# PKG900000001464.net
KiCad netlist of a schematic drawn in EAGLE
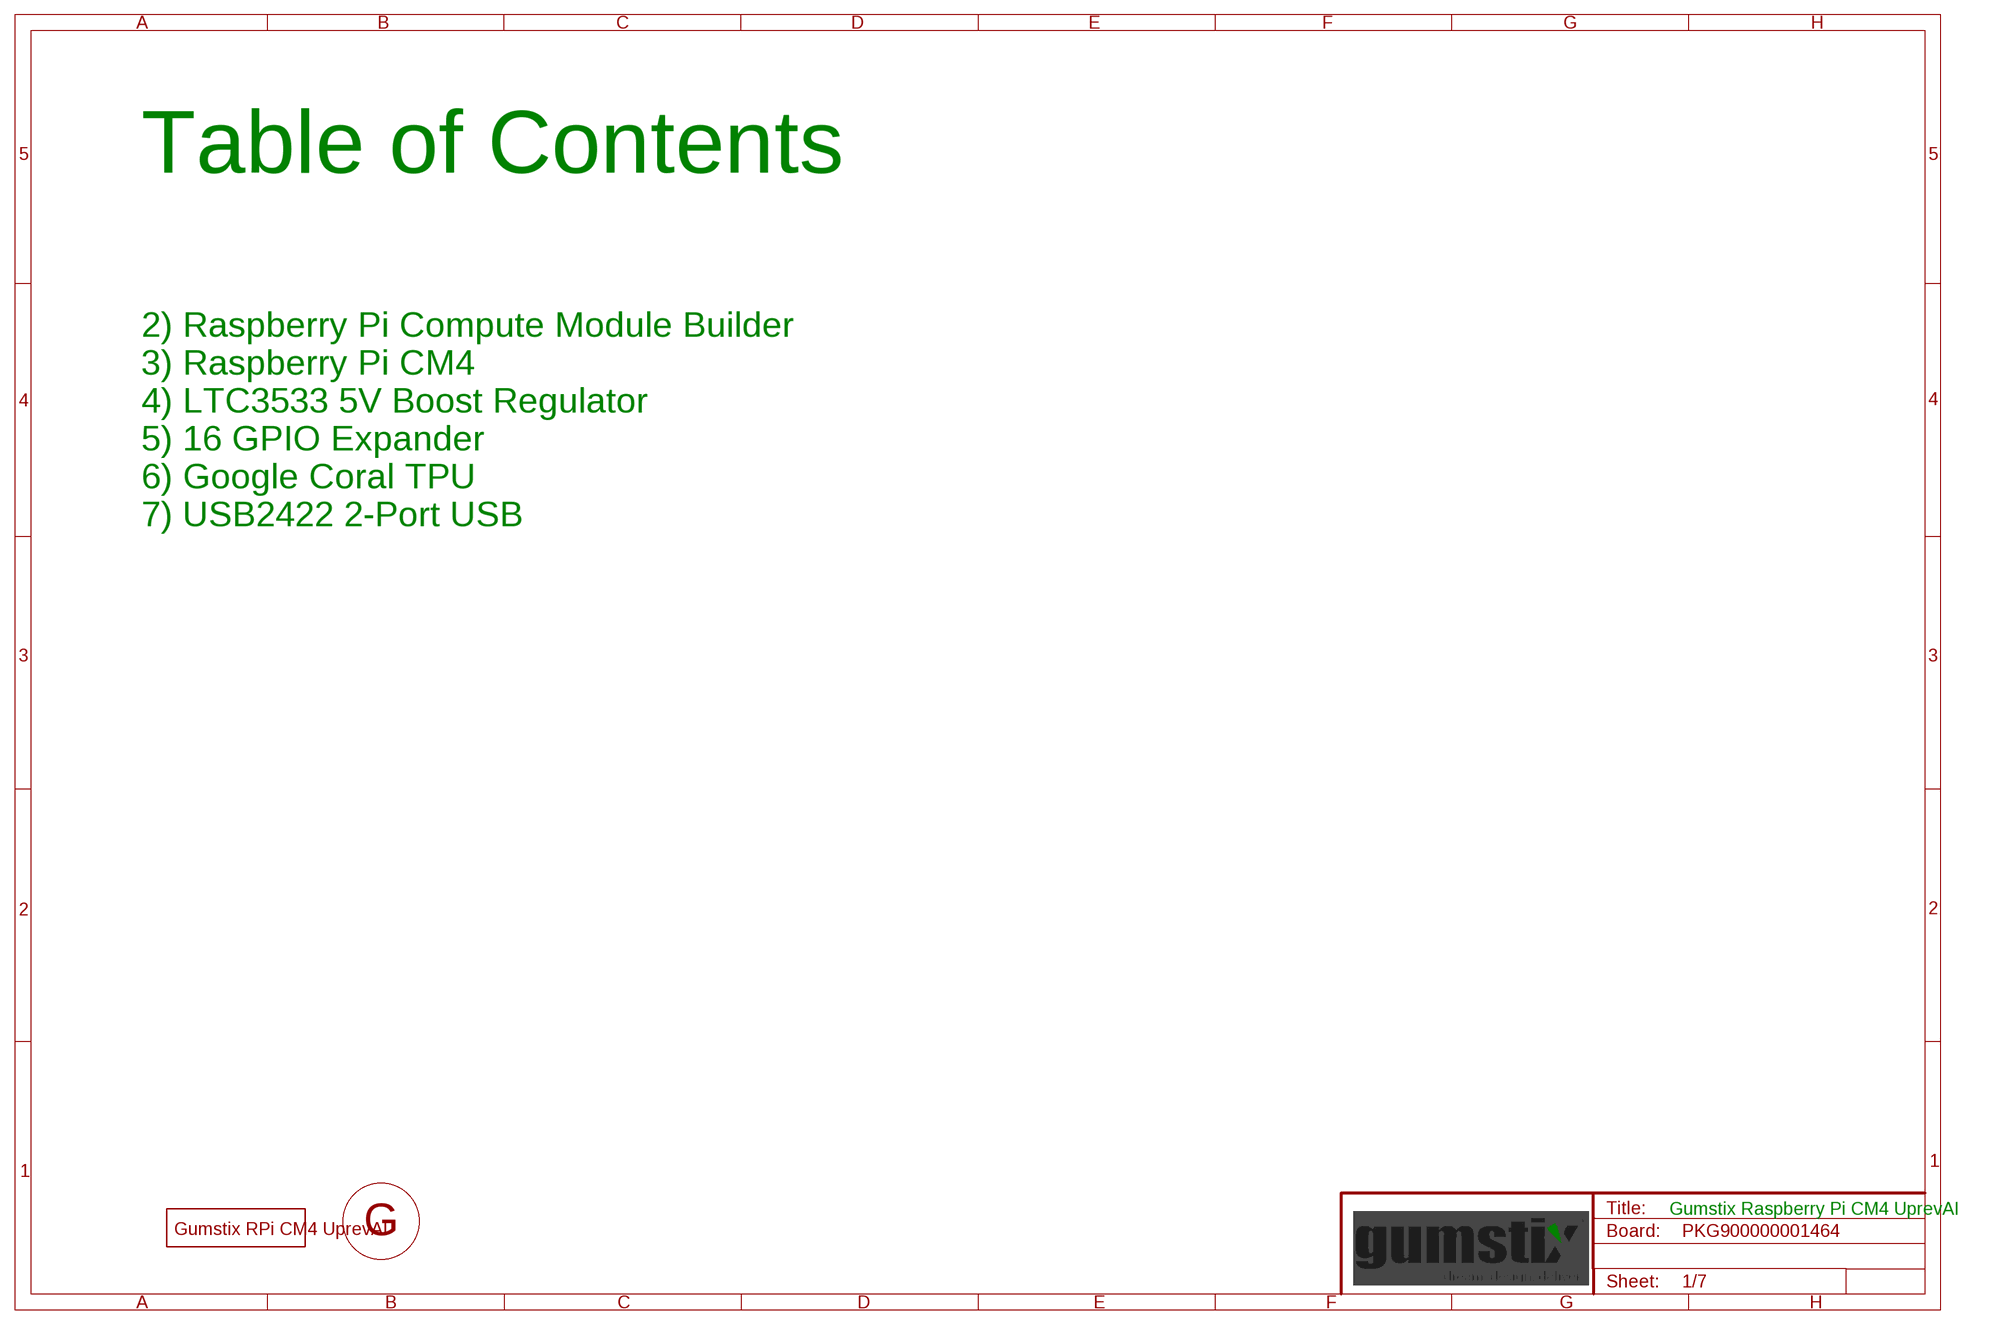
[diagram p0: schematic, sheet 1]
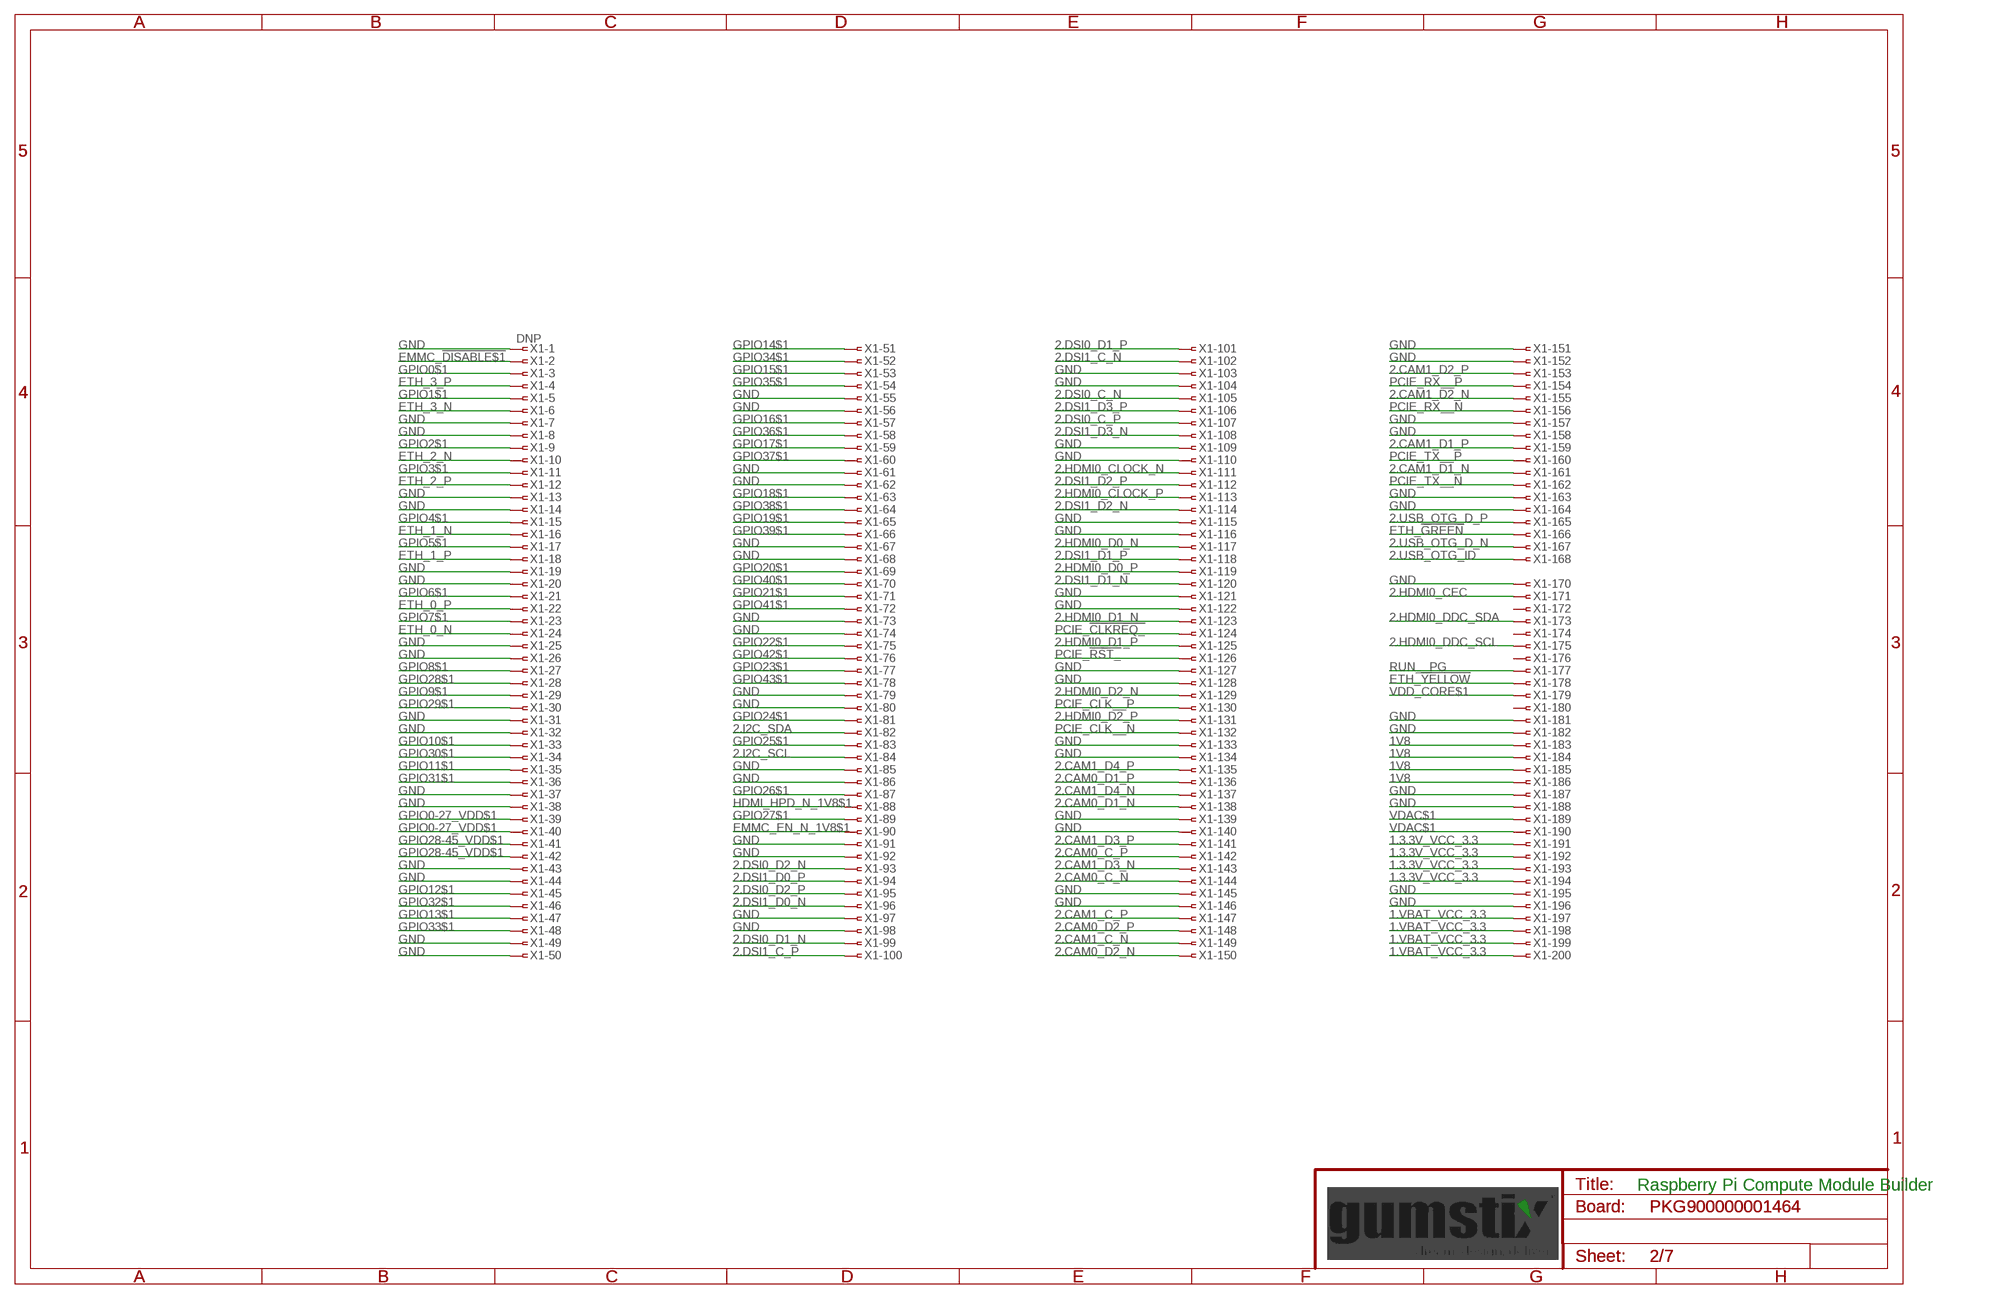
[diagram p1: schematic, sheet 2]
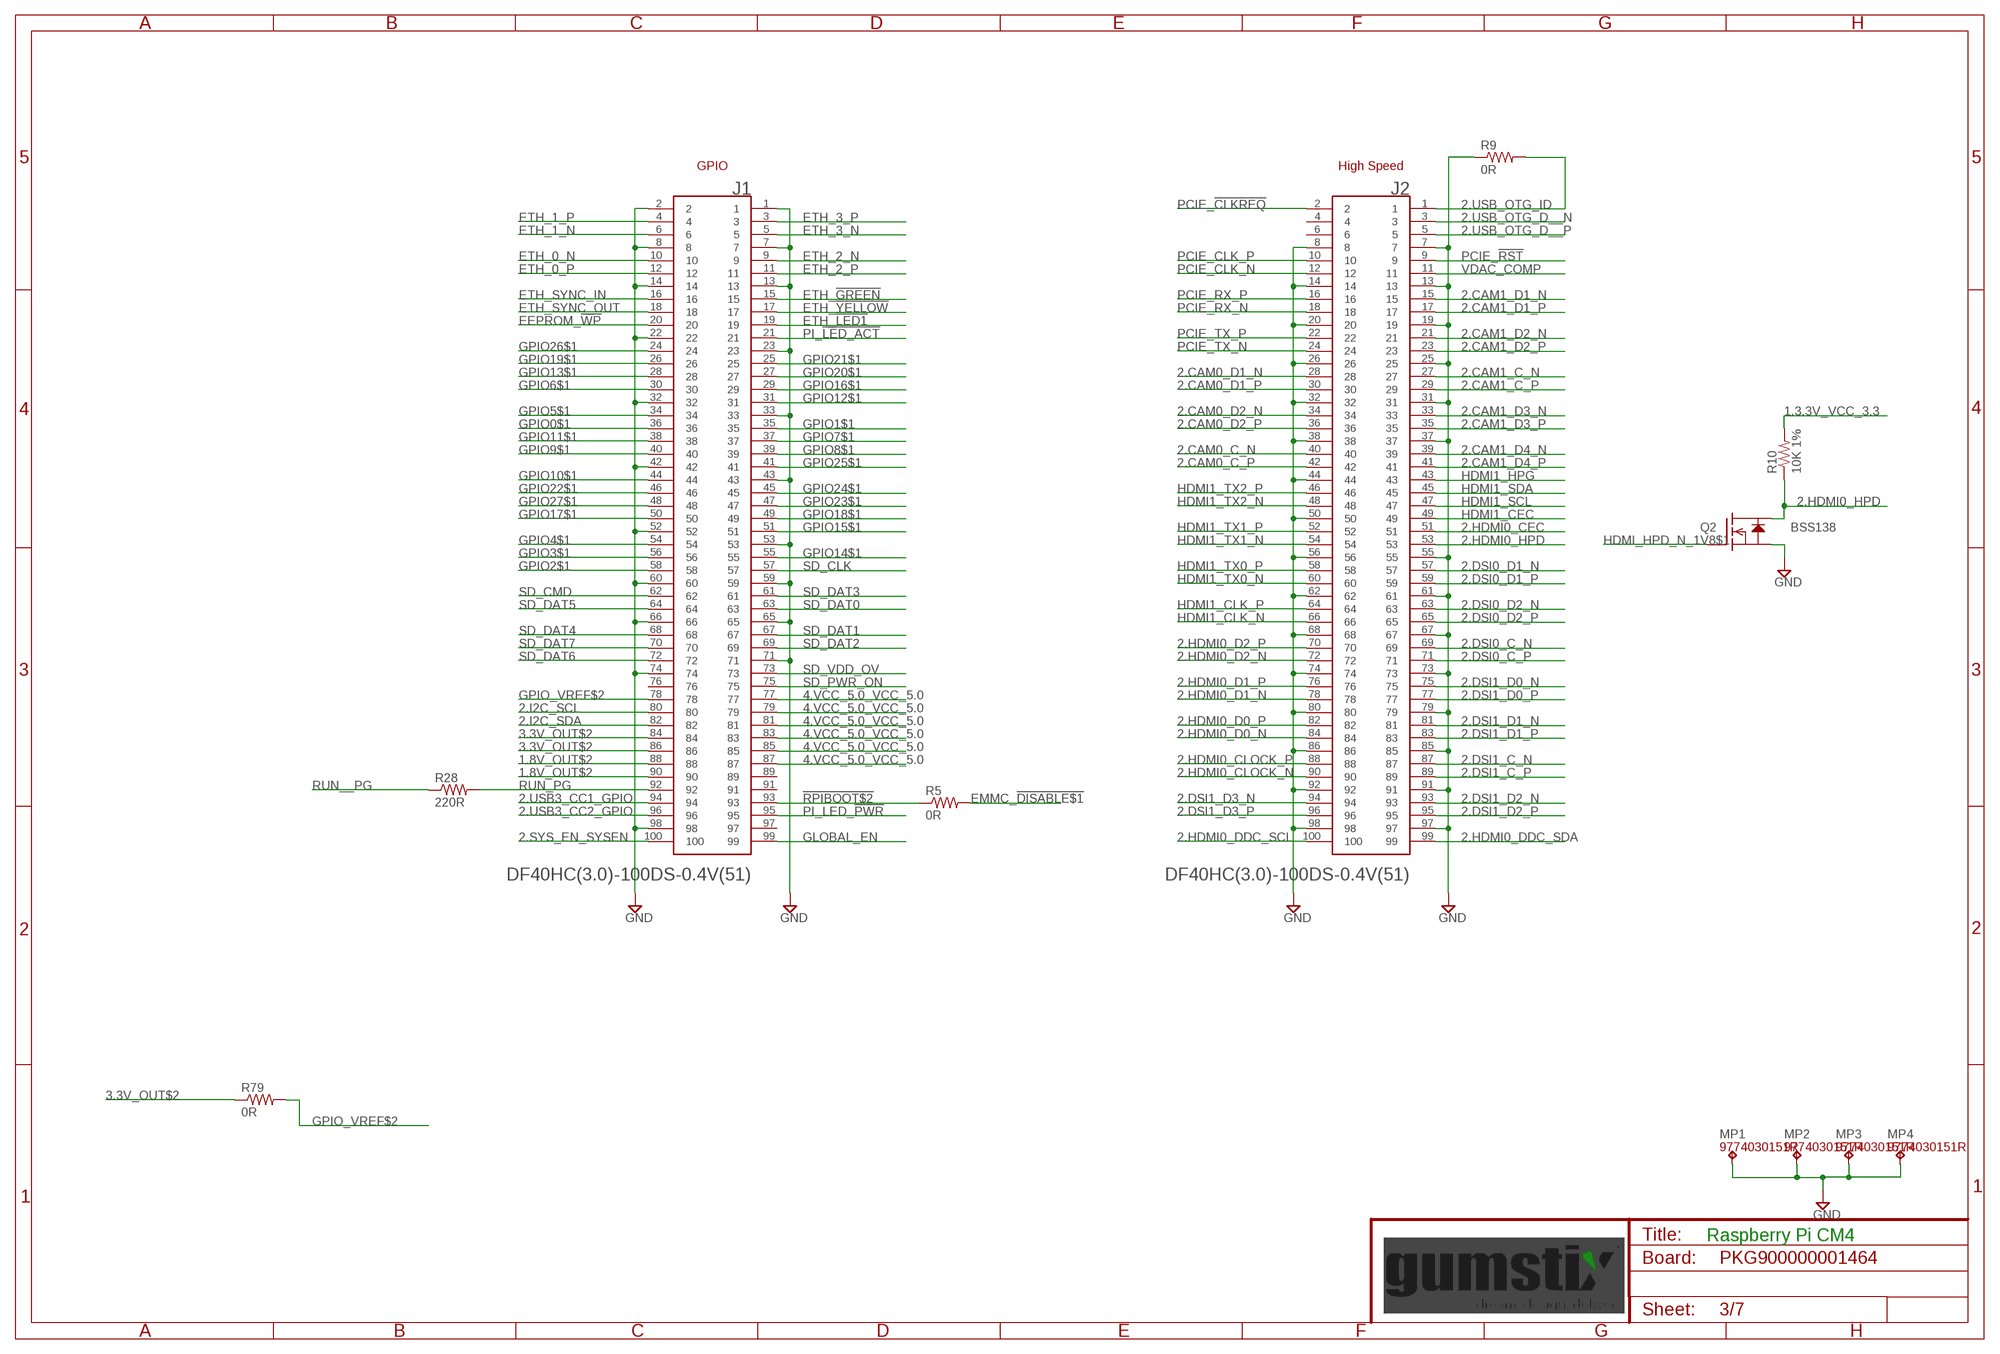
[diagram p2: schematic, sheet 3]
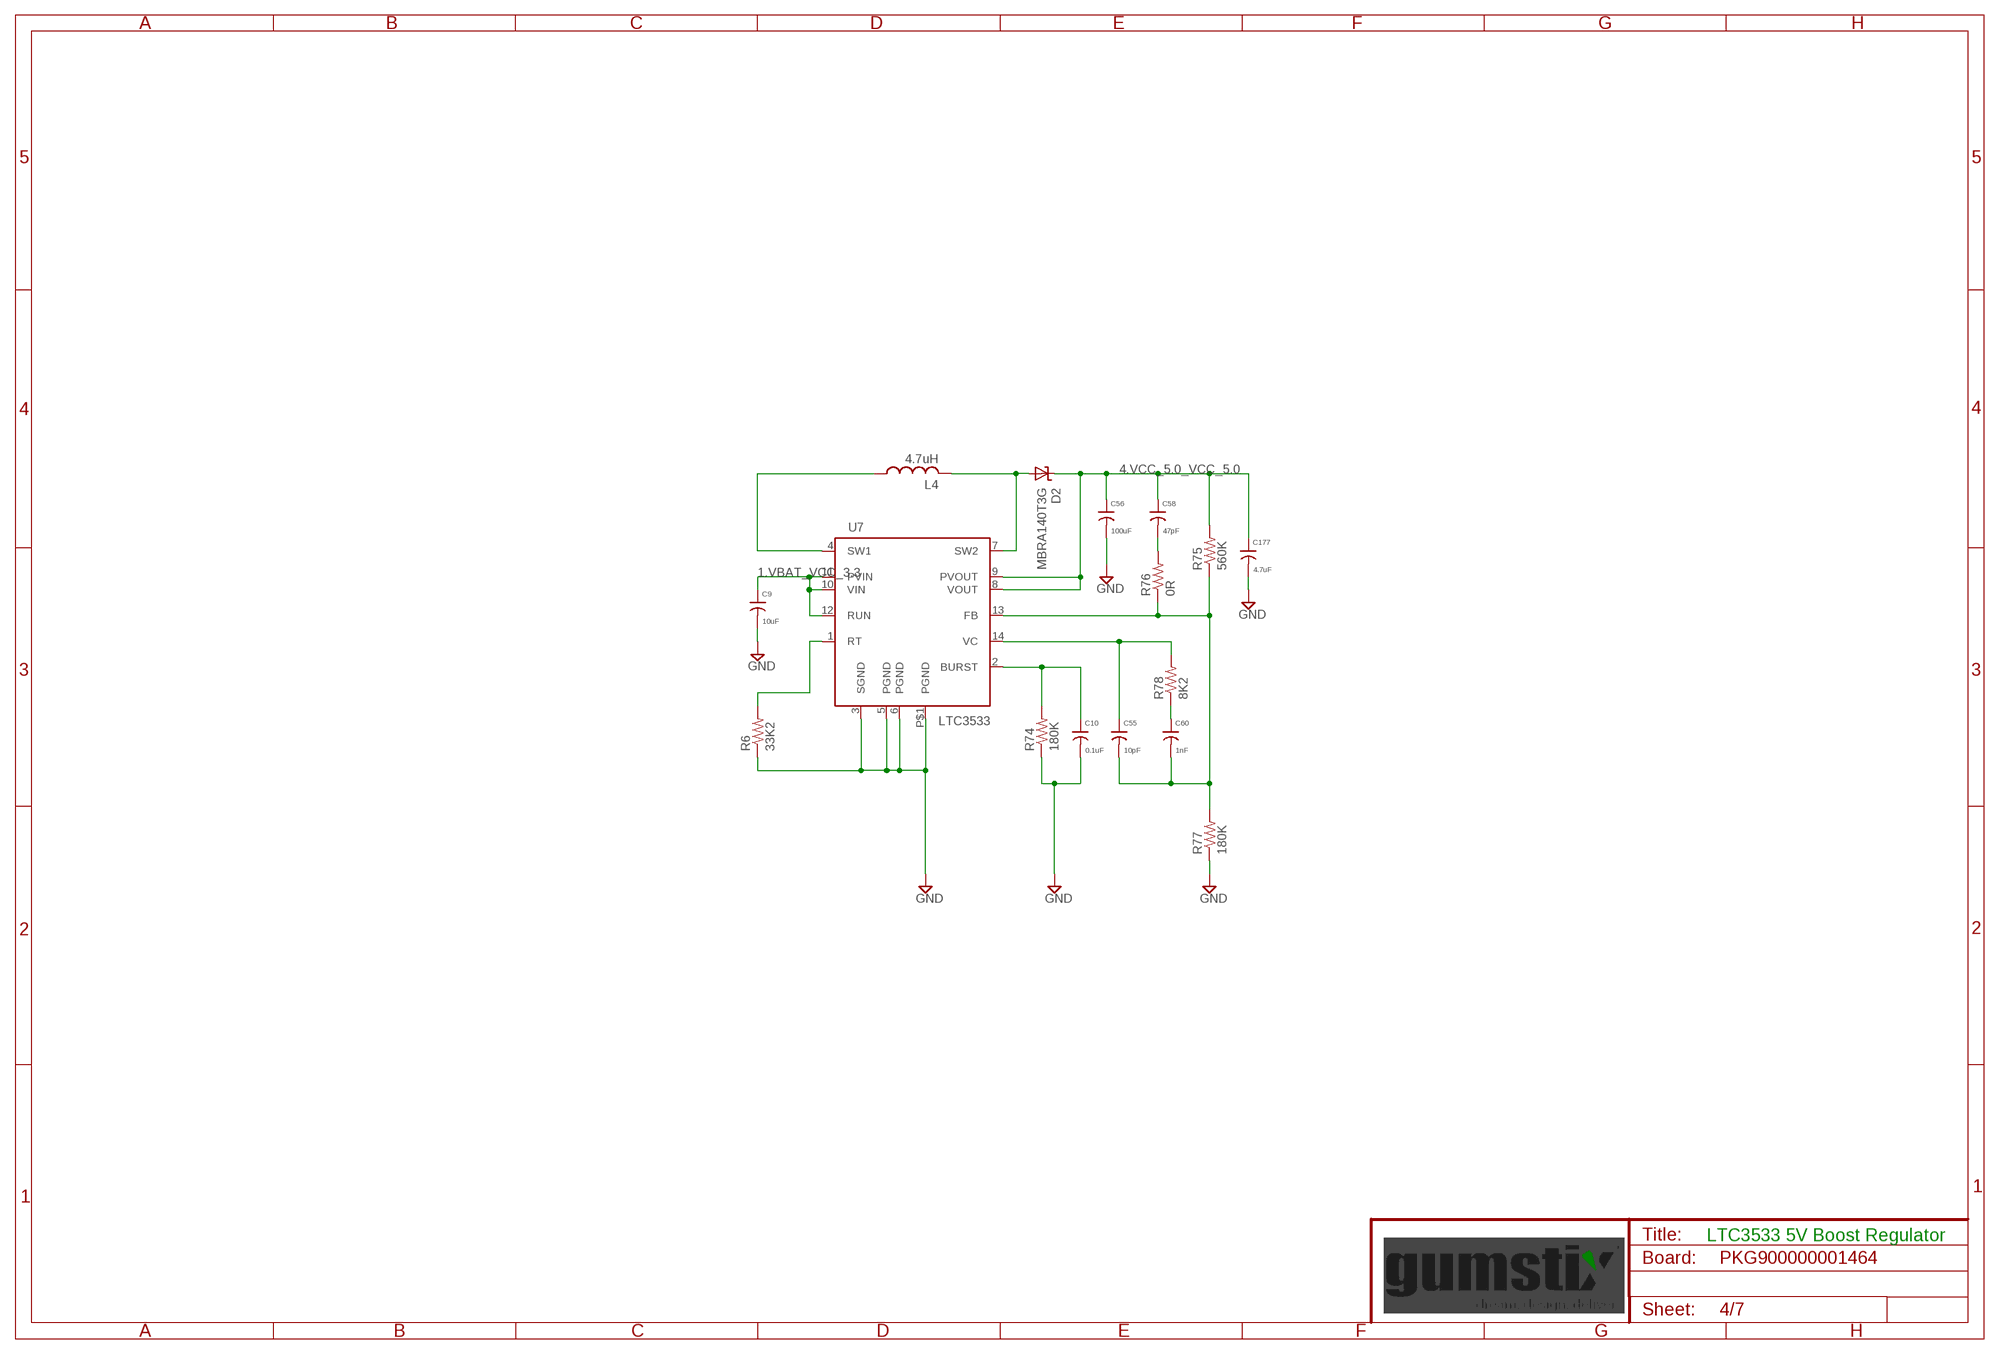
[diagram p3: schematic, sheet 4]
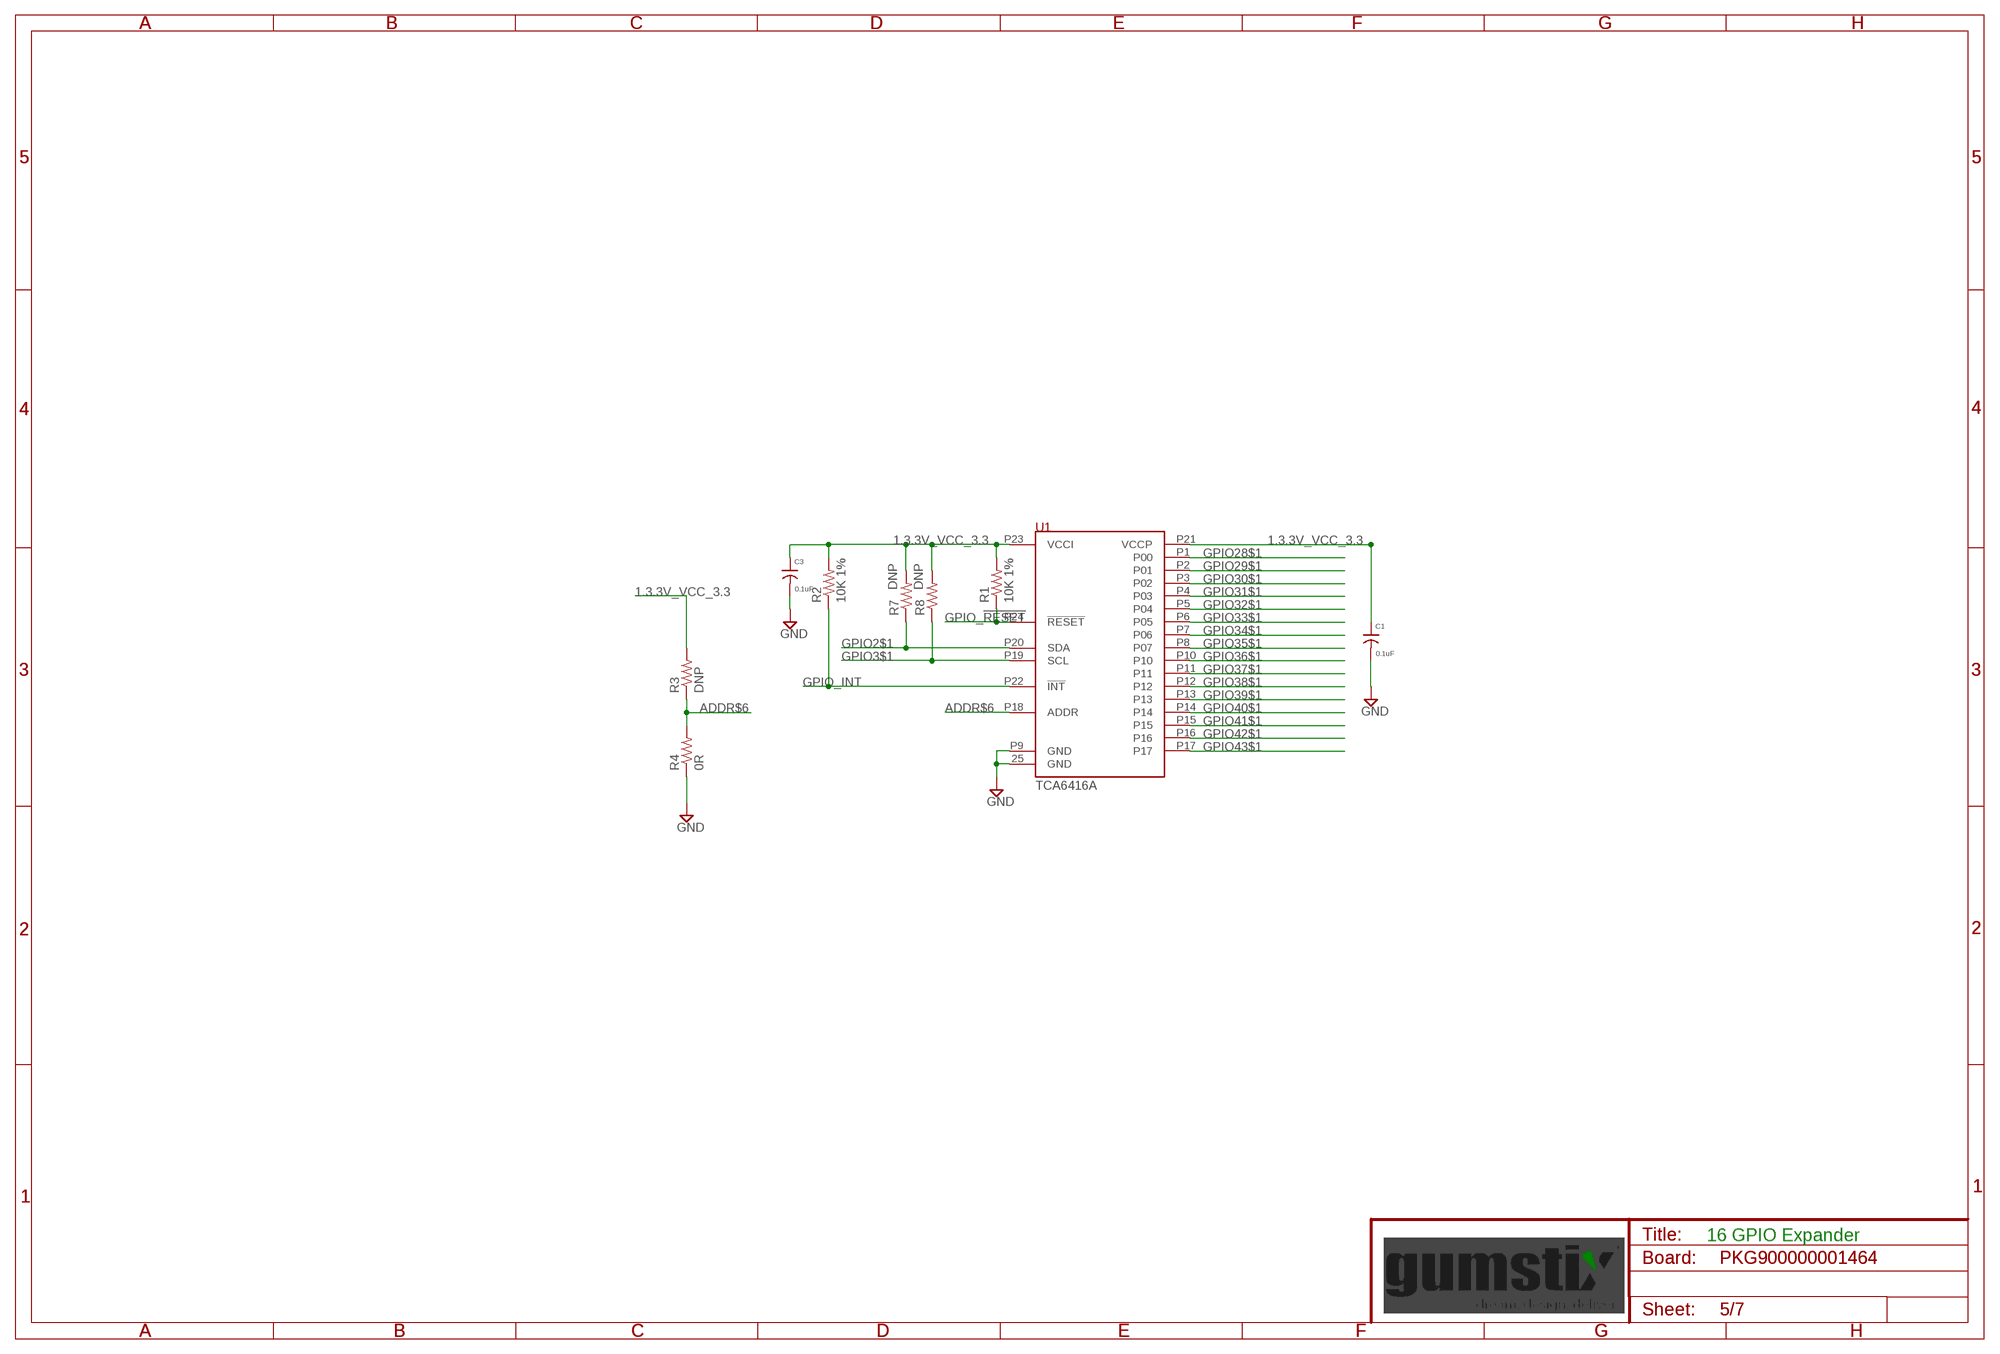
[diagram p4: schematic, sheet 5]
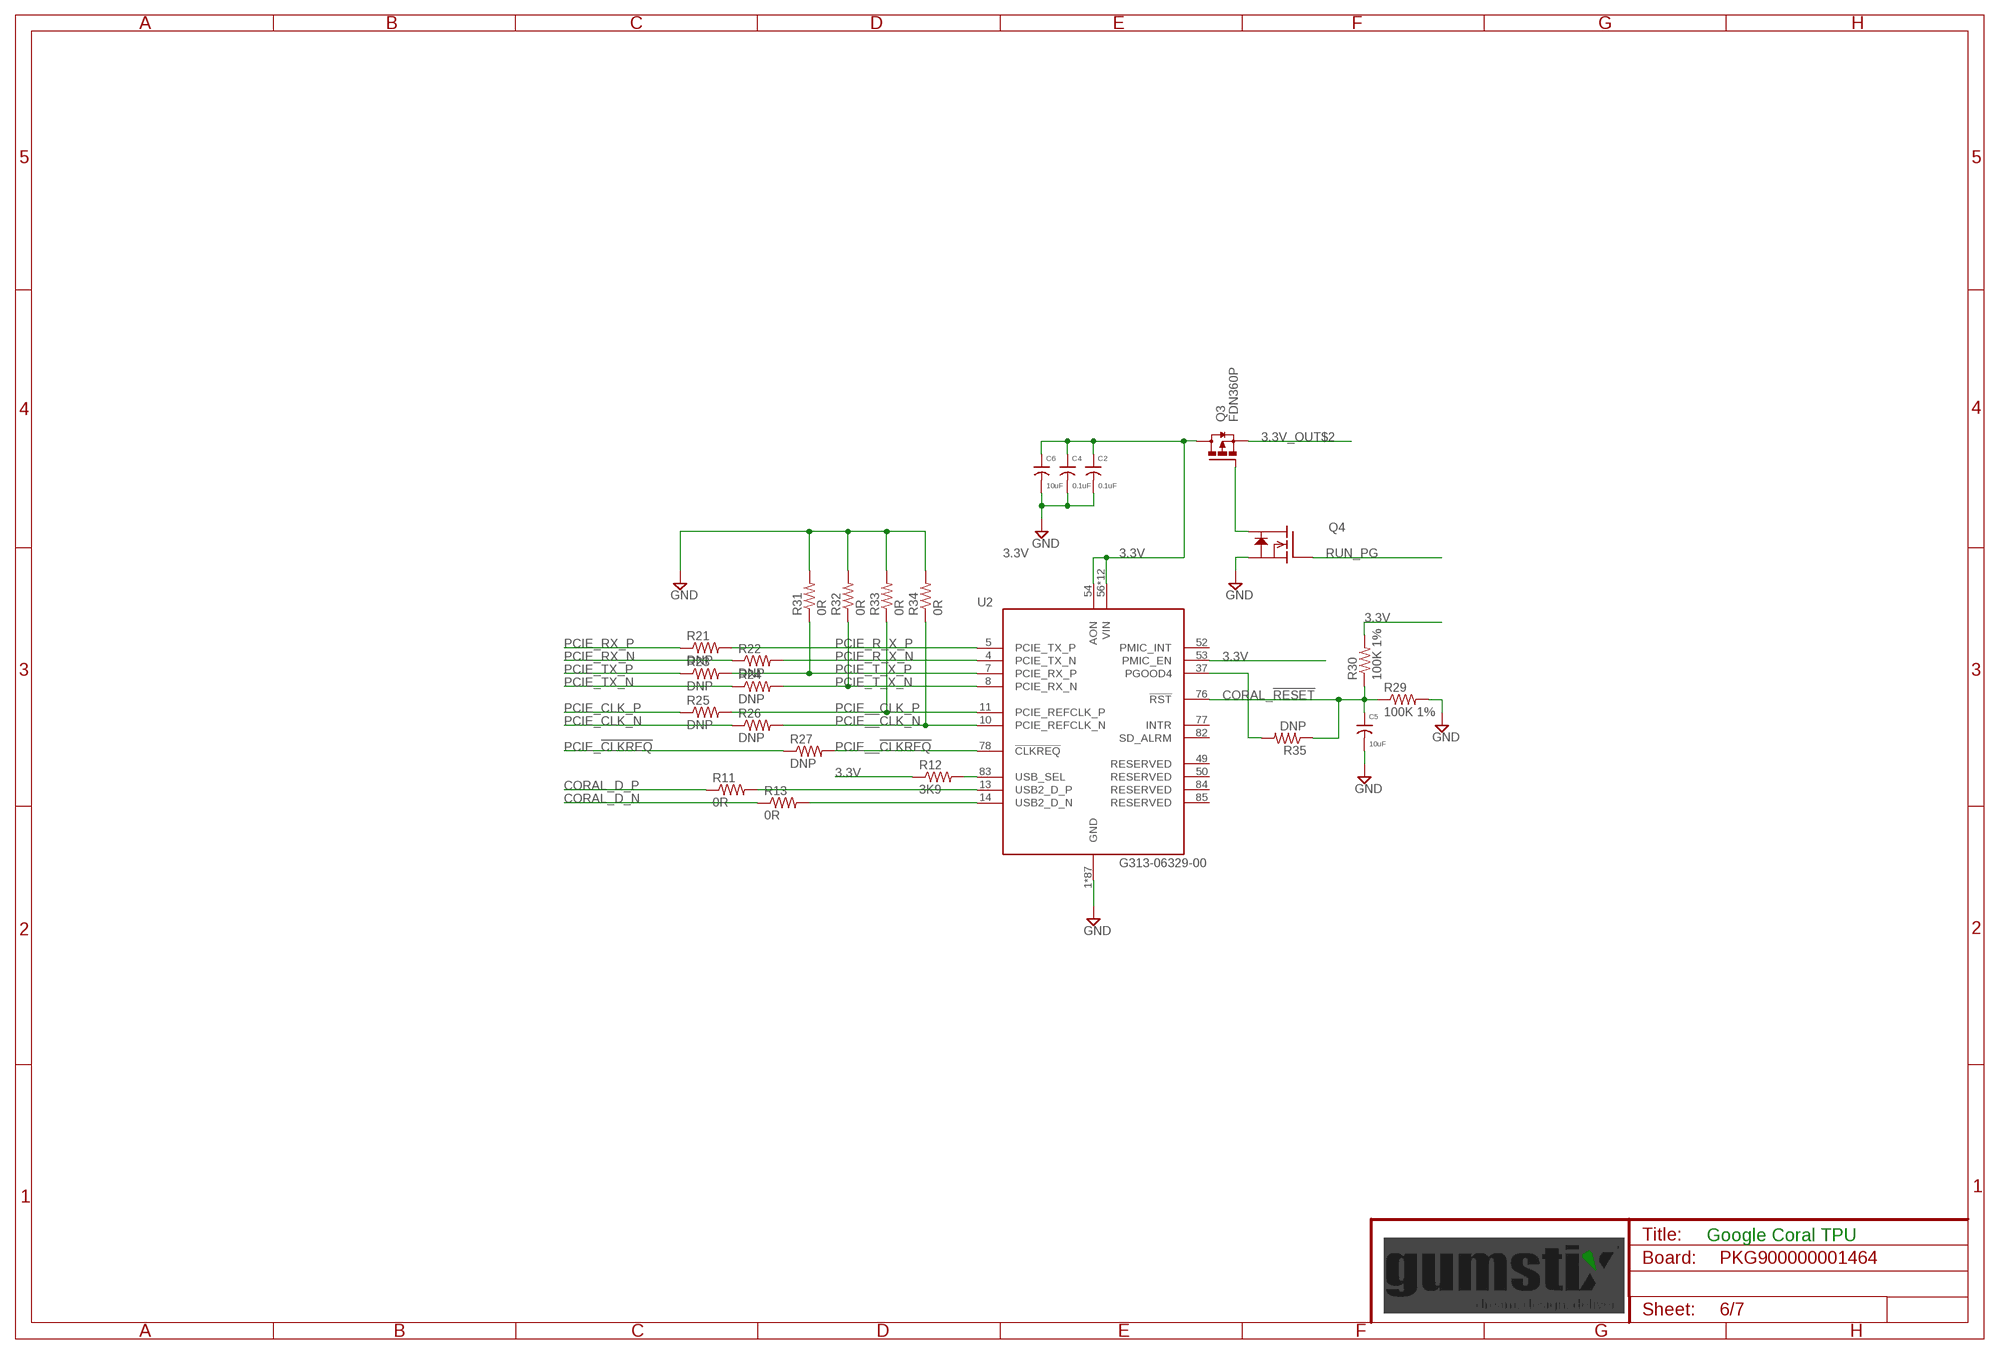
[diagram p5: schematic, sheet 6]
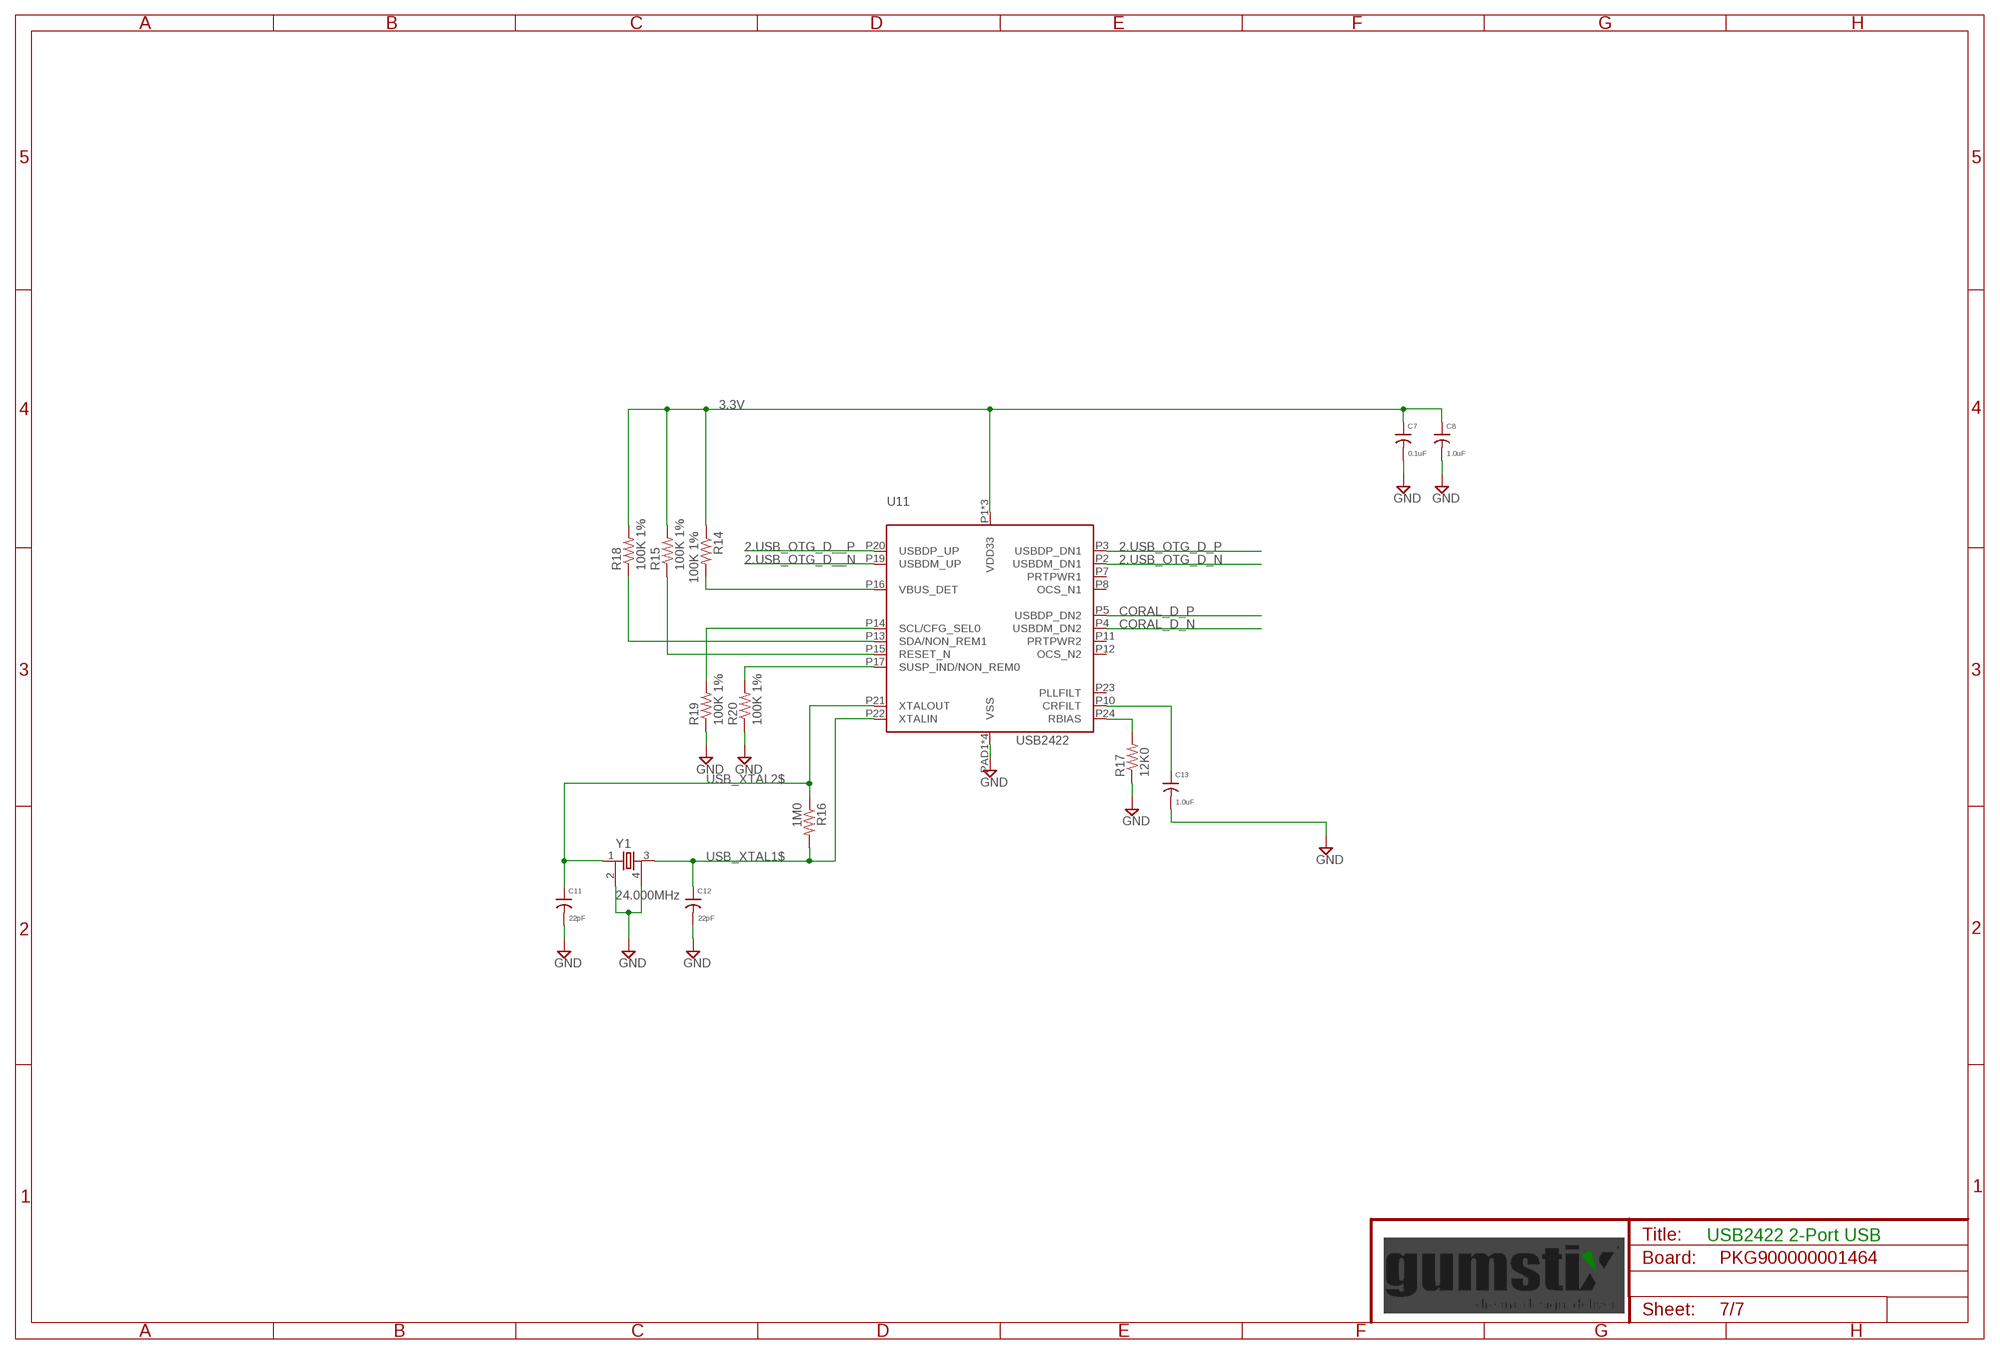
[diagram p6: schematic, sheet 7]

(export (version "E")
  (design (tool "Eeschema 10.0.6"))
  (components
    (comp (ref "C9")
      (value "10uF")
      (footprint "eagle-import:0603")
      (libsource (lib "eagle-import") (part "C0603"))
    )
    (comp (ref "C10")
      (value "0.1uF")
      (footprint "eagle-import:0201")
      (libsource (lib "eagle-import") (part "C0201"))
    )
    (comp (ref "C55")
      (value "10pF")
      (footprint "eagle-import:0201")
      (libsource (lib "eagle-import") (part "C0201"))
    )
    (comp (ref "C56")
      (value "100uF")
      (footprint "eagle-import:1206")
      (libsource (lib "eagle-import") (part "C1206"))
    )
    (comp (ref "C58")
      (value "47pF")
      (footprint "eagle-import:0201")
      (libsource (lib "eagle-import") (part "C0201"))
    )
    (comp (ref "C60")
      (value "1nF")
      (footprint "eagle-import:0402")
      (libsource (lib "eagle-import") (part "C0402"))
    )
    (comp (ref "C177")
      (value "4.7uF")
      (footprint "eagle-import:0603")
      (libsource (lib "eagle-import") (part "C0603"))
    )
    (comp (ref "D2")
      (value "MBRA140T3G")
      (footprint "eagle-import:SMAJ")
      (libsource (lib "eagle-import") (part "DSMA"))
    )
    (comp (ref "L4")
      (value "4.7uH")
      (footprint "eagle-import:B82462")
      (libsource (lib "eagle-import") (part "L82462"))
    )
    (comp (ref "R6")
      (value "33K2")
      (footprint "eagle-import:0402")
      (libsource (lib "eagle-import") (part "R0402"))
    )
    (comp (ref "R74")
      (value "180K")
      (footprint "eagle-import:0201")
      (libsource (lib "eagle-import") (part "R0201"))
    )
    (comp (ref "R75")
      (value "560K")
      (footprint "eagle-import:0402")
      (libsource (lib "eagle-import") (part "R0402"))
    )
    (comp (ref "R76")
      (value "0R")
      (footprint "eagle-import:0201")
      (libsource (lib "eagle-import") (part "R0201"))
    )
    (comp (ref "R77")
      (value "180K")
      (footprint "eagle-import:0201")
      (libsource (lib "eagle-import") (part "R0201"))
    )
    (comp (ref "R78")
      (value "8K2")
      (footprint "eagle-import:0402")
      (libsource (lib "eagle-import") (part "R0402"))
    )
    (comp (ref "U7")
      (value "LTC3533")
      (footprint "eagle-import:DFN-14")
      (libsource (lib "eagle-import") (part "LTC3533"))
    )
    (comp (ref "C1")
      (value "0.1uF")
      (footprint "eagle-import:0201")
      (libsource (lib "eagle-import") (part "C0201"))
    )
    (comp (ref "C3")
      (value "0.1uF")
      (footprint "eagle-import:0201")
      (libsource (lib "eagle-import") (part "C0201"))
    )
    (comp (ref "R1")
      (value "10K 1%")
      (footprint "eagle-import:0201")
      (libsource (lib "eagle-import") (part "R0201"))
    )
    (comp (ref "R2")
      (value "10K 1%")
      (footprint "eagle-import:0201")
      (libsource (lib "eagle-import") (part "R0201"))
    )
    (comp (ref "R3")
      (value "DNP")
      (footprint "eagle-import:0201")
      (libsource (lib "eagle-import") (part "R0201"))
    )
    (comp (ref "R4")
      (value "0R")
      (footprint "eagle-import:0201")
      (libsource (lib "eagle-import") (part "R0201"))
    )
    (comp (ref "R7")
      (value "DNP")
      (footprint "eagle-import:0201")
      (libsource (lib "eagle-import") (part "R0201"))
    )
    (comp (ref "R8")
      (value "DNP")
      (footprint "eagle-import:0201")
      (libsource (lib "eagle-import") (part "R0201"))
    )
    (comp (ref "U1")
      (value "TCA6416A")
      (footprint "eagle-import:WQFN24")
      (libsource (lib "eagle-import") (part "TCA6416A"))
    )
    (comp (ref "C7")
      (value "0.1uF")
      (footprint "eagle-import:0201")
      (libsource (lib "eagle-import") (part "C0201"))
    )
    (comp (ref "C8")
      (value "1.0uF")
      (footprint "eagle-import:0402")
      (libsource (lib "eagle-import") (part "C0402"))
    )
    (comp (ref "C11")
      (value "22pF")
      (footprint "eagle-import:0201")
      (libsource (lib "eagle-import") (part "C0201"))
    )
    (comp (ref "C12")
      (value "22pF")
      (footprint "eagle-import:0201")
      (libsource (lib "eagle-import") (part "C0201"))
    )
    (comp (ref "C13")
      (value "1.0uF")
      (footprint "eagle-import:0402")
      (libsource (lib "eagle-import") (part "C0402"))
    )
    (comp (ref "R14")
      (value "100K 1%")
      (footprint "eagle-import:0201")
      (libsource (lib "eagle-import") (part "R0201"))
    )
    (comp (ref "R15")
      (value "100K 1%")
      (footprint "eagle-import:0201")
      (libsource (lib "eagle-import") (part "R0201"))
    )
    (comp (ref "R16")
      (value "1M0")
      (footprint "eagle-import:0201")
      (libsource (lib "eagle-import") (part "R0201"))
    )
    (comp (ref "R17")
      (value "12K0")
      (footprint "eagle-import:0201")
      (libsource (lib "eagle-import") (part "R0201"))
    )
    (comp (ref "R18")
      (value "100K 1%")
      (footprint "eagle-import:0201")
      (libsource (lib "eagle-import") (part "R0201"))
    )
    (comp (ref "R19")
      (value "100K 1%")
      (footprint "eagle-import:0201")
      (libsource (lib "eagle-import") (part "R0201"))
    )
    (comp (ref "R20")
      (value "100K 1%")
      (footprint "eagle-import:0201")
      (libsource (lib "eagle-import") (part "R0201"))
    )
    (comp (ref "U11")
      (value "USB2422")
      (footprint "eagle-import:VQFN24")
      (libsource (lib "eagle-import") (part "USB2422"))
    )
    (comp (ref "Y1")
      (value "24.000MHz")
      (footprint "eagle-import:CRYSTAL-3225")
      (libsource (lib "eagle-import") (part "Y4CRYSTAL-3225"))
    )
    (comp (ref "J1")
      (value "DF40HC(3.0)-100DS-0.4V(51)")
      (footprint "eagle-import:HRS_DF40C-100DS-0.4V(51)")
      (fields
        (field (name "DIGI-KEY_PART_NUMBER") "H11615CT-ND")
        (field (name "MF") "Hirose")
        (field (name "MP") "DF40C-100DS-0.4V_51_")
      )
      (libsource (lib "eagle-import") (part "DF40C-100DS-0.4V(51)"))
    )
    (comp (ref "J2")
      (value "DF40HC(3.0)-100DS-0.4V(51)")
      (footprint "eagle-import:HRS_DF40C-100DS-0.4V(51)")
      (fields
        (field (name "DIGI-KEY_PART_NUMBER") "H11615CT-ND")
        (field (name "MF") "Hirose")
        (field (name "MP") "DF40C-100DS-0.4V_51_")
      )
      (libsource (lib "eagle-import") (part "DF40C-100DS-0.4V(51)"))
    )
    (comp (ref "MP1")
      (value "9774030151R")
      (footprint "eagle-import:WA-SMSI_9774___151")
      (libsource (lib "eagle-import") (part "BULLET_CONN2.5MM"))
    )
    (comp (ref "MP2")
      (value "9774030151R")
      (footprint "eagle-import:WA-SMSI_9774___151")
      (libsource (lib "eagle-import") (part "BULLET_CONN2.5MM"))
    )
    (comp (ref "MP3")
      (value "9774030151R")
      (footprint "eagle-import:WA-SMSI_9774___151")
      (libsource (lib "eagle-import") (part "BULLET_CONN2.5MM"))
    )
    (comp (ref "MP4")
      (value "9774030151R")
      (footprint "eagle-import:WA-SMSI_9774___151")
      (libsource (lib "eagle-import") (part "BULLET_CONN2.5MM"))
    )
    (comp (ref "Q2")
      (value "BSS138")
      (footprint "eagle-import:SOT23")
      (libsource (lib "eagle-import") (part "BSS138"))
    )
    (comp (ref "R5")
      (value "0R")
      (footprint "eagle-import:0201")
      (libsource (lib "eagle-import") (part "R0201"))
    )
    (comp (ref "R9")
      (value "0R")
      (footprint "eagle-import:0201")
      (libsource (lib "eagle-import") (part "R0201"))
    )
    (comp (ref "R10")
      (value "10K 1%")
      (footprint "eagle-import:0201")
      (libsource (lib "eagle-import") (part "R0201"))
    )
    (comp (ref "R28")
      (value "220R")
      (footprint "eagle-import:0402")
      (libsource (lib "eagle-import") (part "R0402"))
    )
    (comp (ref "R79")
      (value "0R")
      (footprint "eagle-import:0201")
      (libsource (lib "eagle-import") (part "R0201"))
    )
    (comp (ref "C2")
      (value "0.1uF")
      (footprint "eagle-import:0201")
      (libsource (lib "eagle-import") (part "C0201"))
    )
    (comp (ref "C4")
      (value "0.1uF")
      (footprint "eagle-import:0201")
      (libsource (lib "eagle-import") (part "C0201"))
    )
    (comp (ref "C5")
      (value "10uF")
      (footprint "eagle-import:0603")
      (libsource (lib "eagle-import") (part "C0603"))
    )
    (comp (ref "C6")
      (value "10uF")
      (footprint "eagle-import:0603")
      (libsource (lib "eagle-import") (part "C0603"))
    )
    (comp (ref "Q3")
      (value "FDN360P")
      (footprint "eagle-import:SOT23")
      (libsource (lib "eagle-import") (part "MOSFET_P_ENH"))
    )
    (comp (ref "Q4")
      (value "BSS138")
      (footprint "eagle-import:SOT23")
      (libsource (lib "eagle-import") (part "BSS138"))
    )
    (comp (ref "R11")
      (value "0R")
      (footprint "eagle-import:0201")
      (libsource (lib "eagle-import") (part "R0201"))
    )
    (comp (ref "R12")
      (value "3K9")
      (footprint "eagle-import:0201")
      (libsource (lib "eagle-import") (part "R0201"))
    )
    (comp (ref "R13")
      (value "0R")
      (footprint "eagle-import:0201")
      (libsource (lib "eagle-import") (part "R0201"))
    )
    (comp (ref "R21")
      (value "DNP")
      (footprint "eagle-import:0201")
      (libsource (lib "eagle-import") (part "R0201"))
    )
    (comp (ref "R22")
      (value "DNP")
      (footprint "eagle-import:0201")
      (libsource (lib "eagle-import") (part "R0201"))
    )
    (comp (ref "R23")
      (value "DNP")
      (footprint "eagle-import:0201")
      (libsource (lib "eagle-import") (part "R0201"))
    )
    (comp (ref "R24")
      (value "DNP")
      (footprint "eagle-import:0201")
      (libsource (lib "eagle-import") (part "R0201"))
    )
    (comp (ref "R25")
      (value "DNP")
      (footprint "eagle-import:0201")
      (libsource (lib "eagle-import") (part "R0201"))
    )
    (comp (ref "R26")
      (value "DNP")
      (footprint "eagle-import:0201")
      (libsource (lib "eagle-import") (part "R0201"))
    )
    (comp (ref "R27")
      (value "DNP")
      (footprint "eagle-import:0201")
      (libsource (lib "eagle-import") (part "R0201"))
    )
    (comp (ref "R29")
      (value "100K 1%")
      (footprint "eagle-import:0201")
      (libsource (lib "eagle-import") (part "R0201"))
    )
    (comp (ref "R30")
      (value "100K 1%")
      (footprint "eagle-import:0201")
      (libsource (lib "eagle-import") (part "R0201"))
    )
    (comp (ref "R31")
      (value "0R")
      (footprint "eagle-import:0201")
      (libsource (lib "eagle-import") (part "R0201"))
    )
    (comp (ref "R32")
      (value "0R")
      (footprint "eagle-import:0201")
      (libsource (lib "eagle-import") (part "R0201"))
    )
    (comp (ref "R33")
      (value "0R")
      (footprint "eagle-import:0201")
      (libsource (lib "eagle-import") (part "R0201"))
    )
    (comp (ref "R34")
      (value "0R")
      (footprint "eagle-import:0201")
      (libsource (lib "eagle-import") (part "R0201"))
    )
    (comp (ref "R35")
      (value "DNP")
      (footprint "eagle-import:0201")
      (libsource (lib "eagle-import") (part "R0201"))
    )
    (comp (ref "U2")
      (value "G313-06329-00")
      (footprint "eagle-import:G313-06329-00")
      (libsource (lib "eagle-import") (part "G313-06329-00"))
    )
    (comp (ref "X1")
      (value "DNP")
      (footprint "eagle-import:SLOT-1376408-1_1.8V_MOD")
      (libsource (lib "eagle-import") (part "1376408SLOT_1.8V_MOD"))
    )
    (comp (ref "FD1")
      (value "DNP")
      (footprint "eagle-import:FIDUCIAL")
      (libsource (lib "eagle-import") (part "FIDUCIAL"))
    )
    (comp (ref "FD2")
      (value "DNP")
      (footprint "eagle-import:FIDUCIAL")
      (libsource (lib "eagle-import") (part "FIDUCIAL"))
    )
    (comp (ref "FD3")
      (value "DNP")
      (footprint "eagle-import:FIDUCIAL")
      (libsource (lib "eagle-import") (part "FIDUCIAL"))
    )
    (comp (ref "FD4")
      (value "DNP")
      (footprint "eagle-import:FIDUCIAL")
      (libsource (lib "eagle-import") (part "FIDUCIAL"))
    )
    (comp (ref "FD5")
      (value "DNP")
      (footprint "eagle-import:FIDUCIAL")
      (libsource (lib "eagle-import") (part "FIDUCIAL"))
    )
    (comp (ref "FD6")
      (value "DNP")
      (footprint "eagle-import:FIDUCIAL")
      (libsource (lib "eagle-import") (part "FIDUCIAL"))
    )
    (comp (ref "U$3")
      (value "DNP")
      (footprint "eagle-import:GEPPETTO_LABEL")
      (fields
        (field (name "TITLE") "BoardName")
        (field (name "BOARD") "PCB900000001464v3")
        (field (name "TITLE_1") "Gumstix RPi CM4 UprevAI")
        (field (name "YEAR") "2020")
      )
      (libsource (lib "eagle-import") (part "GEPPETTO_LABEL{dblquote}"))
    )
    (comp (ref "U$4")
      (value "DNP")
      (footprint "eagle-import:GEPPETTO_LOGO_SILK10")
      (libsource (lib "eagle-import") (part "GEPPETTO_LOGO10X10"))
    )
  )
  (nets
    (net (code "1") (name "1.3.3V_VCC_3.3") (class "Default")
      (node (ref "C1") (pin "1") (pinfunction "1_1") (pintype "passive"))
      (node (ref "C3") (pin "1") (pinfunction "1_1") (pintype "passive"))
      (node (ref "R1") (pin "2") (pinfunction "2_2") (pintype "passive"))
      (node (ref "R10") (pin "2") (pinfunction "2_2") (pintype "passive"))
      (node (ref "R2") (pin "2") (pinfunction "2_2") (pintype "passive"))
      (node (ref "R3") (pin "2") (pinfunction "2_2") (pintype "passive"))
      (node (ref "R7") (pin "2") (pinfunction "2_2") (pintype "passive"))
      (node (ref "R8") (pin "2") (pinfunction "2_2") (pintype "passive"))
      (node (ref "U1") (pin "P21") (pinfunction "VCCP_P21") (pintype "power_in"))
      (node (ref "U1") (pin "P23") (pinfunction "VCCI_P23") (pintype "power_in"))
      (node (ref "X1") (pin "191") (pinfunction "1_191") (pintype "passive"))
      (node (ref "X1") (pin "192") (pinfunction "1_192") (pintype "passive"))
      (node (ref "X1") (pin "193") (pinfunction "1_193") (pintype "passive"))
      (node (ref "X1") (pin "194") (pinfunction "1_194") (pintype "passive"))
    )
    (net (code "2") (name "1.8V_OUT$2") (class "Default")
      (node (ref "J1") (pin "88") (pinfunction "88_88") (pintype "passive"))
      (node (ref "J1") (pin "90") (pinfunction "90_90") (pintype "passive"))
    )
    (net (code "3") (name "1.VBAT_VCC_3.3") (class "Default")
      (node (ref "C9") (pin "1") (pinfunction "1_1") (pintype "passive"))
      (node (ref "U7") (pin "10") (pinfunction "VIN_10") (pintype "power_in"))
      (node (ref "U7") (pin "11") (pinfunction "PVIN_11") (pintype "power_in"))
      (node (ref "U7") (pin "12") (pinfunction "RUN_12") (pintype "input"))
      (node (ref "X1") (pin "197") (pinfunction "1_197") (pintype "passive"))
      (node (ref "X1") (pin "198") (pinfunction "1_198") (pintype "passive"))
      (node (ref "X1") (pin "199") (pinfunction "1_199") (pintype "passive"))
      (node (ref "X1") (pin "200") (pinfunction "1_200") (pintype "passive"))
    )
    (net (code "4") (name "1V8") (class "Default")
      (node (ref "X1") (pin "183") (pinfunction "1_183") (pintype "passive"))
      (node (ref "X1") (pin "184") (pinfunction "1_184") (pintype "passive"))
      (node (ref "X1") (pin "185") (pinfunction "1_185") (pintype "passive"))
      (node (ref "X1") (pin "186") (pinfunction "1_186") (pintype "passive"))
    )
    (net (code "5") (name "2.CAM0_C_N") (class "Default")
      (node (ref "J2") (pin "40") (pinfunction "40_40") (pintype "passive"))
      (node (ref "X1") (pin "144") (pinfunction "1_144") (pintype "passive"))
    )
    (net (code "6") (name "2.CAM0_C_P") (class "Default")
      (node (ref "J2") (pin "42") (pinfunction "42_42") (pintype "passive"))
      (node (ref "X1") (pin "142") (pinfunction "1_142") (pintype "passive"))
    )
    (net (code "7") (name "2.CAM0_D1_N") (class "Default")
      (node (ref "J2") (pin "28") (pinfunction "28_28") (pintype "passive"))
      (node (ref "X1") (pin "138") (pinfunction "1_138") (pintype "passive"))
    )
    (net (code "8") (name "2.CAM0_D1_P") (class "Default")
      (node (ref "J2") (pin "30") (pinfunction "30_30") (pintype "passive"))
      (node (ref "X1") (pin "136") (pinfunction "1_136") (pintype "passive"))
    )
    (net (code "9") (name "2.CAM0_D2_N") (class "Default")
      (node (ref "J2") (pin "34") (pinfunction "34_34") (pintype "passive"))
      (node (ref "X1") (pin "150") (pinfunction "1_150") (pintype "passive"))
    )
    (net (code "10") (name "2.CAM0_D2_P") (class "Default")
      (node (ref "J2") (pin "36") (pinfunction "36_36") (pintype "passive"))
      (node (ref "X1") (pin "148") (pinfunction "1_148") (pintype "passive"))
    )
    (net (code "11") (name "2.CAM1_C_N") (class "Default")
      (node (ref "J2") (pin "27") (pinfunction "27_27") (pintype "passive"))
      (node (ref "X1") (pin "149") (pinfunction "1_149") (pintype "passive"))
    )
    (net (code "12") (name "2.CAM1_C_P") (class "Default")
      (node (ref "J2") (pin "29") (pinfunction "29_29") (pintype "passive"))
      (node (ref "X1") (pin "147") (pinfunction "1_147") (pintype "passive"))
    )
    (net (code "13") (name "2.CAM1_D1_N") (class "Default")
      (node (ref "J2") (pin "15") (pinfunction "15_15") (pintype "passive"))
      (node (ref "X1") (pin "161") (pinfunction "1_161") (pintype "passive"))
    )
    (net (code "14") (name "2.CAM1_D1_P") (class "Default")
      (node (ref "J2") (pin "17") (pinfunction "17_17") (pintype "passive"))
      (node (ref "X1") (pin "159") (pinfunction "1_159") (pintype "passive"))
    )
    (net (code "15") (name "2.CAM1_D2_N") (class "Default")
      (node (ref "J2") (pin "21") (pinfunction "21_21") (pintype "passive"))
      (node (ref "X1") (pin "155") (pinfunction "1_155") (pintype "passive"))
    )
    (net (code "16") (name "2.CAM1_D2_P") (class "Default")
      (node (ref "J2") (pin "23") (pinfunction "23_23") (pintype "passive"))
      (node (ref "X1") (pin "153") (pinfunction "1_153") (pintype "passive"))
    )
    (net (code "17") (name "2.CAM1_D3_N") (class "Default")
      (node (ref "J2") (pin "33") (pinfunction "33_33") (pintype "passive"))
      (node (ref "X1") (pin "143") (pinfunction "1_143") (pintype "passive"))
    )
    (net (code "18") (name "2.CAM1_D3_P") (class "Default")
      (node (ref "J2") (pin "35") (pinfunction "35_35") (pintype "passive"))
      (node (ref "X1") (pin "141") (pinfunction "1_141") (pintype "passive"))
    )
    (net (code "19") (name "2.CAM1_D4_N") (class "Default")
      (node (ref "J2") (pin "39") (pinfunction "39_39") (pintype "passive"))
      (node (ref "X1") (pin "137") (pinfunction "1_137") (pintype "passive"))
    )
    (net (code "20") (name "2.CAM1_D4_P") (class "Default")
      (node (ref "J2") (pin "41") (pinfunction "41_41") (pintype "passive"))
      (node (ref "X1") (pin "135") (pinfunction "1_135") (pintype "passive"))
    )
    (net (code "21") (name "2.DSI0_C_N") (class "Default")
      (node (ref "J2") (pin "69") (pinfunction "69_69") (pintype "passive"))
      (node (ref "X1") (pin "105") (pinfunction "1_105") (pintype "passive"))
    )
    (net (code "22") (name "2.DSI0_C_P") (class "Default")
      (node (ref "J2") (pin "71") (pinfunction "71_71") (pintype "passive"))
      (node (ref "X1") (pin "107") (pinfunction "1_107") (pintype "passive"))
    )
    (net (code "23") (name "2.DSI0_D1_N") (class "Default")
      (node (ref "J2") (pin "57") (pinfunction "57_57") (pintype "passive"))
      (node (ref "X1") (pin "99") (pinfunction "1_99") (pintype "passive"))
    )
    (net (code "24") (name "2.DSI0_D1_P") (class "Default")
      (node (ref "J2") (pin "59") (pinfunction "59_59") (pintype "passive"))
      (node (ref "X1") (pin "101") (pinfunction "1_101") (pintype "passive"))
    )
    (net (code "25") (name "2.DSI0_D2_N") (class "Default")
      (node (ref "J2") (pin "63") (pinfunction "63_63") (pintype "passive"))
      (node (ref "X1") (pin "93") (pinfunction "1_93") (pintype "passive"))
    )
    (net (code "26") (name "2.DSI0_D2_P") (class "Default")
      (node (ref "J2") (pin "65") (pinfunction "65_65") (pintype "passive"))
      (node (ref "X1") (pin "95") (pinfunction "1_95") (pintype "passive"))
    )
    (net (code "27") (name "2.DSI1_C_N") (class "Default")
      (node (ref "J2") (pin "87") (pinfunction "87_87") (pintype "passive"))
      (node (ref "X1") (pin "102") (pinfunction "1_102") (pintype "passive"))
    )
    (net (code "28") (name "2.DSI1_C_P") (class "Default")
      (node (ref "J2") (pin "89") (pinfunction "89_89") (pintype "passive"))
      (node (ref "X1") (pin "100") (pinfunction "1_100") (pintype "passive"))
    )
    (net (code "29") (name "2.DSI1_D0_N") (class "Default")
      (node (ref "J2") (pin "75") (pinfunction "75_75") (pintype "passive"))
      (node (ref "X1") (pin "96") (pinfunction "1_96") (pintype "passive"))
    )
    (net (code "30") (name "2.DSI1_D0_P") (class "Default")
      (node (ref "J2") (pin "77") (pinfunction "77_77") (pintype "passive"))
      (node (ref "X1") (pin "94") (pinfunction "1_94") (pintype "passive"))
    )
    (net (code "31") (name "2.DSI1_D1_N") (class "Default")
      (node (ref "J2") (pin "81") (pinfunction "81_81") (pintype "passive"))
      (node (ref "X1") (pin "120") (pinfunction "1_120") (pintype "passive"))
    )
    (net (code "32") (name "2.DSI1_D1_P") (class "Default")
      (node (ref "J2") (pin "83") (pinfunction "83_83") (pintype "passive"))
      (node (ref "X1") (pin "118") (pinfunction "1_118") (pintype "passive"))
    )
    (net (code "33") (name "2.DSI1_D2_N") (class "Default")
      (node (ref "J2") (pin "93") (pinfunction "93_93") (pintype "passive"))
      (node (ref "X1") (pin "114") (pinfunction "1_114") (pintype "passive"))
    )
    (net (code "34") (name "2.DSI1_D2_P") (class "Default")
      (node (ref "J2") (pin "95") (pinfunction "95_95") (pintype "passive"))
      (node (ref "X1") (pin "112") (pinfunction "1_112") (pintype "passive"))
    )
    (net (code "35") (name "2.DSI1_D3_N") (class "Default")
      (node (ref "J2") (pin "94") (pinfunction "94_94") (pintype "passive"))
      (node (ref "X1") (pin "108") (pinfunction "1_108") (pintype "passive"))
    )
    (net (code "36") (name "2.DSI1_D3_P") (class "Default")
      (node (ref "J2") (pin "96") (pinfunction "96_96") (pintype "passive"))
      (node (ref "X1") (pin "106") (pinfunction "1_106") (pintype "passive"))
    )
    (net (code "37") (name "2.HDMI0_CEC") (class "Default")
      (node (ref "J2") (pin "51") (pinfunction "51_51") (pintype "passive"))
      (node (ref "X1") (pin "171") (pinfunction "1_171") (pintype "passive"))
    )
    (net (code "38") (name "2.HDMI0_CLOCK_N") (class "Default")
      (node (ref "J2") (pin "90") (pinfunction "90_90") (pintype "passive"))
      (node (ref "X1") (pin "111") (pinfunction "1_111") (pintype "passive"))
    )
    (net (code "39") (name "2.HDMI0_CLOCK_P") (class "Default")
      (node (ref "J2") (pin "88") (pinfunction "88_88") (pintype "passive"))
      (node (ref "X1") (pin "113") (pinfunction "1_113") (pintype "passive"))
    )
    (net (code "40") (name "2.HDMI0_D0_N") (class "Default")
      (node (ref "J2") (pin "84") (pinfunction "84_84") (pintype "passive"))
      (node (ref "X1") (pin "117") (pinfunction "1_117") (pintype "passive"))
    )
    (net (code "41") (name "2.HDMI0_D0_P") (class "Default")
      (node (ref "J2") (pin "82") (pinfunction "82_82") (pintype "passive"))
      (node (ref "X1") (pin "119") (pinfunction "1_119") (pintype "passive"))
    )
    (net (code "42") (name "2.HDMI0_D1_N") (class "Default")
      (node (ref "J2") (pin "78") (pinfunction "78_78") (pintype "passive"))
      (node (ref "X1") (pin "123") (pinfunction "1_123") (pintype "passive"))
    )
    (net (code "43") (name "2.HDMI0_D1_P") (class "Default")
      (node (ref "J2") (pin "76") (pinfunction "76_76") (pintype "passive"))
      (node (ref "X1") (pin "125") (pinfunction "1_125") (pintype "passive"))
    )
    (net (code "44") (name "2.HDMI0_D2_N") (class "Default")
      (node (ref "J2") (pin "72") (pinfunction "72_72") (pintype "passive"))
      (node (ref "X1") (pin "129") (pinfunction "1_129") (pintype "passive"))
    )
    (net (code "45") (name "2.HDMI0_D2_P") (class "Default")
      (node (ref "J2") (pin "70") (pinfunction "70_70") (pintype "passive"))
      (node (ref "X1") (pin "131") (pinfunction "1_131") (pintype "passive"))
    )
    (net (code "46") (name "2.HDMI0_DDC_SCL") (class "Default")
      (node (ref "J2") (pin "100") (pinfunction "100_100") (pintype "passive"))
      (node (ref "X1") (pin "175") (pinfunction "1_175") (pintype "passive"))
    )
    (net (code "47") (name "2.HDMI0_DDC_SDA") (class "Default")
      (node (ref "J2") (pin "99") (pinfunction "99_99") (pintype "passive"))
      (node (ref "X1") (pin "173") (pinfunction "1_173") (pintype "passive"))
    )
    (net (code "48") (name "2.HDMI0_HPD") (class "Default")
      (node (ref "J2") (pin "53") (pinfunction "53_53") (pintype "passive"))
      (node (ref "Q2") (pin "3") (pinfunction "D_3") (pintype "passive"))
      (node (ref "R10") (pin "1") (pinfunction "1_1") (pintype "passive"))
    )
    (net (code "49") (name "2.I2C_SCL") (class "Default")
      (node (ref "J1") (pin "80") (pinfunction "80_80") (pintype "passive"))
      (node (ref "X1") (pin "84") (pinfunction "1_84") (pintype "passive"))
    )
    (net (code "50") (name "2.I2C_SDA") (class "Default")
      (node (ref "J1") (pin "82") (pinfunction "82_82") (pintype "passive"))
      (node (ref "X1") (pin "82") (pinfunction "1_82") (pintype "passive"))
    )
    (net (code "51") (name "2.SYS_EN_SYSEN") (class "Default")
      (node (ref "J1") (pin "100") (pinfunction "100_100") (pintype "passive"))
    )
    (net (code "52") (name "2.USB3_CC1_GPIO") (class "Default")
      (node (ref "J1") (pin "94") (pinfunction "94_94") (pintype "passive"))
    )
    (net (code "53") (name "2.USB3_CC2_GPIO") (class "Default")
      (node (ref "J1") (pin "96") (pinfunction "96_96") (pintype "passive"))
    )
    (net (code "54") (name "2.USB_OTG_D_N") (class "Default")
      (node (ref "U11") (pin "P2") (pinfunction "USBDM_DN1_P2") (pintype "bidirectional"))
      (node (ref "X1") (pin "167") (pinfunction "1_167") (pintype "passive"))
    )
    (net (code "55") (name "2.USB_OTG_D_P") (class "Default")
      (node (ref "U11") (pin "P3") (pinfunction "USBDP_DN1_P3") (pintype "bidirectional"))
      (node (ref "X1") (pin "165") (pinfunction "1_165") (pintype "passive"))
    )
    (net (code "56") (name "2.USB_OTG_D__N") (class "Default")
      (node (ref "J2") (pin "3") (pinfunction "3_3") (pintype "passive"))
      (node (ref "U11") (pin "P19") (pinfunction "USBDM_UP_P19") (pintype "bidirectional"))
    )
    (net (code "57") (name "2.USB_OTG_D__P") (class "Default")
      (node (ref "J2") (pin "5") (pinfunction "5_5") (pintype "passive"))
      (node (ref "U11") (pin "P20") (pinfunction "USBDP_UP_P20") (pintype "bidirectional"))
    )
    (net (code "58") (name "2.USB_OTG_ID") (class "Default")
      (node (ref "J2") (pin "1") (pinfunction "1_1") (pintype "passive"))
      (node (ref "R9") (pin "2") (pinfunction "2_2") (pintype "passive"))
      (node (ref "X1") (pin "168") (pinfunction "1_168") (pintype "passive"))
    )
    (net (code "59") (name "3.3V") (class "Default")
      (node (ref "C2") (pin "1") (pinfunction "1_1") (pintype "passive"))
      (node (ref "C4") (pin "1") (pinfunction "1_1") (pintype "passive"))
      (node (ref "C6") (pin "1") (pinfunction "1_1") (pintype "passive"))
      (node (ref "C7") (pin "1") (pinfunction "1_1") (pintype "passive"))
      (node (ref "C8") (pin "1") (pinfunction "1_1") (pintype "passive"))
      (node (ref "Q3") (pin "3") (pinfunction "D_3") (pintype "passive"))
      (node (ref "R12") (pin "1") (pinfunction "1_1") (pintype "passive"))
      (node (ref "R14") (pin "1") (pinfunction "1_1") (pintype "passive"))
      (node (ref "R15") (pin "2") (pinfunction "2_2") (pintype "passive"))
      (node (ref "R18") (pin "2") (pinfunction "2_2") (pintype "passive"))
      (node (ref "R30") (pin "2") (pinfunction "2_2") (pintype "passive"))
      (node (ref "U11") (pin "P1") (pinfunction "VDD33_P1") (pintype "power_in"))
      (node (ref "U11") (pin "P18") (pinfunction "VDD33_P18") (pintype "power_in"))
      (node (ref "U11") (pin "P9") (pinfunction "VDD33_P9") (pintype "power_in"))
      (node (ref "U2") (pin "53") (pinfunction "PMIC_EN_53") (pintype "bidirectional"))
      (node (ref "U2") (pin "54") (pinfunction "AON_54") (pintype "bidirectional"))
      (node (ref "U2") (pin "56") (pinfunction "VIN_56") (pintype "bidirectional"))
      (node (ref "U2") (pin "57") (pinfunction "VIN_57") (pintype "bidirectional"))
      (node (ref "U2") (pin "58") (pinfunction "VIN_58") (pintype "bidirectional"))
      (node (ref "U2") (pin "59") (pinfunction "VIN_59") (pintype "bidirectional"))
      (node (ref "U2") (pin "60") (pinfunction "VIN_60") (pintype "bidirectional"))
      (node (ref "U2") (pin "61") (pinfunction "VIN_61") (pintype "bidirectional"))
      (node (ref "U2") (pin "62") (pinfunction "VIN_62") (pintype "bidirectional"))
      (node (ref "U2") (pin "63") (pinfunction "VIN_63") (pintype "bidirectional"))
      (node (ref "U2") (pin "64") (pinfunction "VIN_64") (pintype "bidirectional"))
      (node (ref "U2") (pin "65") (pinfunction "VIN_65") (pintype "bidirectional"))
      (node (ref "U2") (pin "66") (pinfunction "VIN_66") (pintype "bidirectional"))
      (node (ref "U2") (pin "67") (pinfunction "VIN_67") (pintype "bidirectional"))
    )
    (net (code "60") (name "3.3V_OUT$2") (class "Default")
      (node (ref "J1") (pin "84") (pinfunction "84_84") (pintype "passive"))
      (node (ref "J1") (pin "86") (pinfunction "86_86") (pintype "passive"))
      (node (ref "Q3") (pin "2") (pinfunction "S_2") (pintype "passive"))
      (node (ref "R79") (pin "1") (pinfunction "1_1") (pintype "passive"))
    )
    (net (code "61") (name "4.VCC_5.0_VCC_5.0") (class "Default")
      (node (ref "C177") (pin "1") (pinfunction "1_1") (pintype "passive"))
      (node (ref "C56") (pin "1") (pinfunction "1_1") (pintype "passive"))
      (node (ref "C58") (pin "1") (pinfunction "1_1") (pintype "passive"))
      (node (ref "D2") (pin "C") (pinfunction "C_C") (pintype "passive"))
      (node (ref "J1") (pin "77") (pinfunction "77_77") (pintype "passive"))
      (node (ref "J1") (pin "79") (pinfunction "79_79") (pintype "passive"))
      (node (ref "J1") (pin "81") (pinfunction "81_81") (pintype "passive"))
      (node (ref "J1") (pin "83") (pinfunction "83_83") (pintype "passive"))
      (node (ref "J1") (pin "85") (pinfunction "85_85") (pintype "passive"))
      (node (ref "J1") (pin "87") (pinfunction "87_87") (pintype "passive"))
      (node (ref "R75") (pin "2") (pinfunction "2_2") (pintype "passive"))
      (node (ref "U7") (pin "8") (pinfunction "VOUT_8") (pintype "input"))
      (node (ref "U7") (pin "9") (pinfunction "PVOUT_9") (pintype "output"))
    )
    (net (code "62") (name "ADDR$6") (class "Default")
      (node (ref "R3") (pin "1") (pinfunction "1_1") (pintype "passive"))
      (node (ref "R4") (pin "2") (pinfunction "2_2") (pintype "passive"))
      (node (ref "U1") (pin "P18") (pinfunction "ADDR_P18") (pintype "bidirectional"))
    )
    (net (code "63") (name "CORAL_D_N") (class "Default")
      (node (ref "R13") (pin "1") (pinfunction "1_1") (pintype "passive"))
      (node (ref "U11") (pin "P4") (pinfunction "USBDM_DN2_P4") (pintype "bidirectional"))
    )
    (net (code "64") (name "CORAL_D_P") (class "Default")
      (node (ref "R11") (pin "1") (pinfunction "1_1") (pintype "passive"))
      (node (ref "U11") (pin "P5") (pinfunction "USBDP_DN2_P5") (pintype "bidirectional"))
    )
    (net (code "65") (name "CORAL_~{RESET}") (class "Default")
      (node (ref "C5") (pin "1") (pinfunction "1_1") (pintype "passive"))
      (node (ref "R29") (pin "1") (pinfunction "1_1") (pintype "passive"))
      (node (ref "R30") (pin "1") (pinfunction "1_1") (pintype "passive"))
      (node (ref "R35") (pin "1") (pinfunction "1_1") (pintype "passive"))
      (node (ref "U2") (pin "76") (pinfunction "~{RST}_76") (pintype "bidirectional"))
    )
    (net (code "66") (name "EEPROM_~{WP}") (class "Default")
      (node (ref "J1") (pin "20") (pinfunction "20_20") (pintype "passive"))
    )
    (net (code "67") (name "EMMC_EN_N_1V8$1") (class "Default")
      (node (ref "X1") (pin "90") (pinfunction "1_90") (pintype "passive"))
    )
    (net (code "68") (name "EMMC_~{DISABLE$1}") (class "Default")
      (node (ref "R5") (pin "2") (pinfunction "2_2") (pintype "passive"))
      (node (ref "X1") (pin "2") (pinfunction "1_2") (pintype "passive"))
    )
    (net (code "69") (name "ETH_0_N") (class "Default")
      (node (ref "J1") (pin "10") (pinfunction "10_10") (pintype "passive"))
      (node (ref "X1") (pin "24") (pinfunction "1_24") (pintype "passive"))
    )
    (net (code "70") (name "ETH_0_P") (class "Default")
      (node (ref "J1") (pin "12") (pinfunction "12_12") (pintype "passive"))
      (node (ref "X1") (pin "22") (pinfunction "1_22") (pintype "passive"))
    )
    (net (code "71") (name "ETH_1_N") (class "Default")
      (node (ref "J1") (pin "6") (pinfunction "6_6") (pintype "passive"))
      (node (ref "X1") (pin "16") (pinfunction "1_16") (pintype "passive"))
    )
    (net (code "72") (name "ETH_1_P") (class "Default")
      (node (ref "J1") (pin "4") (pinfunction "4_4") (pintype "passive"))
      (node (ref "X1") (pin "18") (pinfunction "1_18") (pintype "passive"))
    )
    (net (code "73") (name "ETH_2_N") (class "Default")
      (node (ref "J1") (pin "9") (pinfunction "9_9") (pintype "passive"))
      (node (ref "X1") (pin "10") (pinfunction "1_10") (pintype "passive"))
    )
    (net (code "74") (name "ETH_2_P") (class "Default")
      (node (ref "J1") (pin "11") (pinfunction "11_11") (pintype "passive"))
      (node (ref "X1") (pin "12") (pinfunction "1_12") (pintype "passive"))
    )
    (net (code "75") (name "ETH_3_N") (class "Default")
      (node (ref "J1") (pin "5") (pinfunction "5_5") (pintype "passive"))
      (node (ref "X1") (pin "6") (pinfunction "1_6") (pintype "passive"))
    )
    (net (code "76") (name "ETH_3_P") (class "Default")
      (node (ref "J1") (pin "3") (pinfunction "3_3") (pintype "passive"))
      (node (ref "X1") (pin "4") (pinfunction "1_4") (pintype "passive"))
    )
    (net (code "77") (name "ETH_SYNC_IN") (class "Default")
      (node (ref "J1") (pin "16") (pinfunction "16_16") (pintype "passive"))
    )
    (net (code "78") (name "ETH_SYNC_OUT") (class "Default")
      (node (ref "J1") (pin "18") (pinfunction "18_18") (pintype "passive"))
    )
    (net (code "79") (name "ETH_~{GREEN}") (class "Default")
      (node (ref "J1") (pin "15") (pinfunction "15_15") (pintype "passive"))
      (node (ref "X1") (pin "166") (pinfunction "1_166") (pintype "passive"))
    )
    (net (code "80") (name "ETH_~{LED1}") (class "Default")
      (node (ref "J1") (pin "19") (pinfunction "19_19") (pintype "passive"))
    )
    (net (code "81") (name "ETH_~{YELLOW}") (class "Default")
      (node (ref "J1") (pin "17") (pinfunction "17_17") (pintype "passive"))
      (node (ref "X1") (pin "178") (pinfunction "1_178") (pintype "passive"))
    )
    (net (code "82") (name "GLOBAL_EN") (class "Default")
      (node (ref "J1") (pin "99") (pinfunction "99_99") (pintype "passive"))
    )
    (net (code "83") (name "GND") (class "Default")
      (node (ref "C1") (pin "2") (pinfunction "2_2") (pintype "passive"))
      (node (ref "C10") (pin "2") (pinfunction "2_2") (pintype "passive"))
      (node (ref "C11") (pin "2") (pinfunction "2_2") (pintype "passive"))
      (node (ref "C12") (pin "2") (pinfunction "2_2") (pintype "passive"))
      (node (ref "C13") (pin "2") (pinfunction "2_2") (pintype "passive"))
      (node (ref "C177") (pin "2") (pinfunction "2_2") (pintype "passive"))
      (node (ref "C2") (pin "2") (pinfunction "2_2") (pintype "passive"))
      (node (ref "C3") (pin "2") (pinfunction "2_2") (pintype "passive"))
      (node (ref "C4") (pin "2") (pinfunction "2_2") (pintype "passive"))
      (node (ref "C5") (pin "2") (pinfunction "2_2") (pintype "passive"))
      (node (ref "C56") (pin "2") (pinfunction "2_2") (pintype "passive"))
      (node (ref "C6") (pin "2") (pinfunction "2_2") (pintype "passive"))
      (node (ref "C7") (pin "2") (pinfunction "2_2") (pintype "passive"))
      (node (ref "C8") (pin "2") (pinfunction "2_2") (pintype "passive"))
      (node (ref "C9") (pin "2") (pinfunction "2_2") (pintype "passive"))
      (node (ref "J1") (pin "1") (pinfunction "1_1") (pintype "passive"))
      (node (ref "J1") (pin "13") (pinfunction "13_13") (pintype "passive"))
      (node (ref "J1") (pin "14") (pinfunction "14_14") (pintype "passive"))
      (node (ref "J1") (pin "2") (pinfunction "2_2") (pintype "passive"))
      (node (ref "J1") (pin "22") (pinfunction "22_22") (pintype "passive"))
      (node (ref "J1") (pin "23") (pinfunction "23_23") (pintype "passive"))
      (node (ref "J1") (pin "32") (pinfunction "32_32") (pintype "passive"))
      (node (ref "J1") (pin "33") (pinfunction "33_33") (pintype "passive"))
      (node (ref "J1") (pin "42") (pinfunction "42_42") (pintype "passive"))
      (node (ref "J1") (pin "43") (pinfunction "43_43") (pintype "passive"))
      (node (ref "J1") (pin "52") (pinfunction "52_52") (pintype "passive"))
      (node (ref "J1") (pin "53") (pinfunction "53_53") (pintype "passive"))
      (node (ref "J1") (pin "59") (pinfunction "59_59") (pintype "passive"))
      (node (ref "J1") (pin "60") (pinfunction "60_60") (pintype "passive"))
      (node (ref "J1") (pin "65") (pinfunction "65_65") (pintype "passive"))
      (node (ref "J1") (pin "66") (pinfunction "66_66") (pintype "passive"))
      (node (ref "J1") (pin "7") (pinfunction "7_7") (pintype "passive"))
      (node (ref "J1") (pin "71") (pinfunction "71_71") (pintype "passive"))
      (node (ref "J1") (pin "74") (pinfunction "74_74") (pintype "passive"))
      (node (ref "J1") (pin "8") (pinfunction "8_8") (pintype "passive"))
      (node (ref "J1") (pin "98") (pinfunction "98_98") (pintype "passive"))
      (node (ref "J2") (pin "13") (pinfunction "13_13") (pintype "passive"))
      (node (ref "J2") (pin "14") (pinfunction "14_14") (pintype "passive"))
      (node (ref "J2") (pin "19") (pinfunction "19_19") (pintype "passive"))
      (node (ref "J2") (pin "20") (pinfunction "20_20") (pintype "passive"))
      (node (ref "J2") (pin "25") (pinfunction "25_25") (pintype "passive"))
      (node (ref "J2") (pin "26") (pinfunction "26_26") (pintype "passive"))
      (node (ref "J2") (pin "31") (pinfunction "31_31") (pintype "passive"))
      (node (ref "J2") (pin "32") (pinfunction "32_32") (pintype "passive"))
      (node (ref "J2") (pin "37") (pinfunction "37_37") (pintype "passive"))
      (node (ref "J2") (pin "38") (pinfunction "38_38") (pintype "passive"))
      (node (ref "J2") (pin "44") (pinfunction "44_44") (pintype "passive"))
      (node (ref "J2") (pin "50") (pinfunction "50_50") (pintype "passive"))
      (node (ref "J2") (pin "55") (pinfunction "55_55") (pintype "passive"))
      (node (ref "J2") (pin "56") (pinfunction "56_56") (pintype "passive"))
      (node (ref "J2") (pin "61") (pinfunction "61_61") (pintype "passive"))
      (node (ref "J2") (pin "62") (pinfunction "62_62") (pintype "passive"))
      (node (ref "J2") (pin "67") (pinfunction "67_67") (pintype "passive"))
      (node (ref "J2") (pin "68") (pinfunction "68_68") (pintype "passive"))
      (node (ref "J2") (pin "7") (pinfunction "7_7") (pintype "passive"))
      (node (ref "J2") (pin "73") (pinfunction "73_73") (pintype "passive"))
      (node (ref "J2") (pin "74") (pinfunction "74_74") (pintype "passive"))
      (node (ref "J2") (pin "79") (pinfunction "79_79") (pintype "passive"))
      (node (ref "J2") (pin "8") (pinfunction "8_8") (pintype "passive"))
      (node (ref "J2") (pin "80") (pinfunction "80_80") (pintype "passive"))
      (node (ref "J2") (pin "85") (pinfunction "85_85") (pintype "passive"))
      (node (ref "J2") (pin "86") (pinfunction "86_86") (pintype "passive"))
      (node (ref "J2") (pin "91") (pinfunction "91_91") (pintype "passive"))
      (node (ref "J2") (pin "92") (pinfunction "92_92") (pintype "passive"))
      (node (ref "J2") (pin "97") (pinfunction "97_97") (pintype "passive"))
      (node (ref "J2") (pin "98") (pinfunction "98_98") (pintype "passive"))
      (node (ref "MP1") (pin "1") (pinfunction "TP_1") (pintype "bidirectional"))
      (node (ref "MP2") (pin "1") (pinfunction "TP_1") (pintype "bidirectional"))
      (node (ref "MP3") (pin "1") (pinfunction "TP_1") (pintype "bidirectional"))
      (node (ref "MP4") (pin "1") (pinfunction "TP_1") (pintype "bidirectional"))
      (node (ref "Q2") (pin "2") (pinfunction "S_2") (pintype "passive"))
      (node (ref "Q4") (pin "2") (pinfunction "S_2") (pintype "passive"))
      (node (ref "R17") (pin "1") (pinfunction "1_1") (pintype "passive"))
      (node (ref "R19") (pin "1") (pinfunction "1_1") (pintype "passive"))
      (node (ref "R20") (pin "1") (pinfunction "1_1") (pintype "passive"))
      (node (ref "R29") (pin "2") (pinfunction "2_2") (pintype "passive"))
      (node (ref "R31") (pin "2") (pinfunction "2_2") (pintype "passive"))
      (node (ref "R32") (pin "2") (pinfunction "2_2") (pintype "passive"))
      (node (ref "R33") (pin "2") (pinfunction "2_2") (pintype "passive"))
      (node (ref "R34") (pin "2") (pinfunction "2_2") (pintype "passive"))
      (node (ref "R4") (pin "1") (pinfunction "1_1") (pintype "passive"))
      (node (ref "R6") (pin "1") (pinfunction "1_1") (pintype "passive"))
      (node (ref "R74") (pin "1") (pinfunction "1_1") (pintype "passive"))
      (node (ref "R77") (pin "1") (pinfunction "1_1") (pintype "passive"))
      (node (ref "R9") (pin "1") (pinfunction "1_1") (pintype "passive"))
      (node (ref "U1") (pin "25") (pinfunction "GND_25") (pintype "power_in"))
      (node (ref "U1") (pin "P9") (pinfunction "GND_P9") (pintype "power_in"))
      (node (ref "U11") (pin "PAD1") (pinfunction "VSS_PAD1") (pintype "power_in"))
      (node (ref "U11") (pin "PAD2") (pinfunction "VSS_PAD2") (pintype "power_in"))
      (node (ref "U11") (pin "PAD3") (pinfunction "VSS_PAD3") (pintype "power_in"))
      (node (ref "U11") (pin "PAD4") (pinfunction "VSS_PAD4") (pintype "power_in"))
      (node (ref "U2") (pin "1") (pinfunction "GND_1") (pintype "bidirectional"))
      (node (ref "U2") (pin "100") (pinfunction "GND_100") (pintype "bidirectional"))
      (node (ref "U2") (pin "101") (pinfunction "GND_101") (pintype "bidirectional"))
      (node (ref "U2") (pin "102") (pinfunction "GND_102") (pintype "bidirectional"))
      (node (ref "U2") (pin "103") (pinfunction "GND_103") (pintype "bidirectional"))
      (node (ref "U2") (pin "104") (pinfunction "GND_104") (pintype "bidirectional"))
      (node (ref "U2") (pin "105") (pinfunction "GND_105") (pintype "bidirectional"))
      (node (ref "U2") (pin "106") (pinfunction "GND_106") (pintype "bidirectional"))
      (node (ref "U2") (pin "107") (pinfunction "GND_107") (pintype "bidirectional"))
      (node (ref "U2") (pin "108") (pinfunction "GND_108") (pintype "bidirectional"))
      (node (ref "U2") (pin "109") (pinfunction "GND_109") (pintype "bidirectional"))
      (node (ref "U2") (pin "110") (pinfunction "GND_110") (pintype "bidirectional"))
      (node (ref "U2") (pin "111") (pinfunction "GND_111") (pintype "bidirectional"))
      (node (ref "U2") (pin "112") (pinfunction "GND_112") (pintype "bidirectional"))
      (node (ref "U2") (pin "113") (pinfunction "GND_113") (pintype "bidirectional"))
      (node (ref "U2") (pin "114") (pinfunction "GND_114") (pintype "bidirectional"))
      (node (ref "U2") (pin "115") (pinfunction "GND_115") (pintype "bidirectional"))
      (node (ref "U2") (pin "116") (pinfunction "GND_116") (pintype "bidirectional"))
      (node (ref "U2") (pin "117") (pinfunction "GND_117") (pintype "bidirectional"))
      (node (ref "U2") (pin "118") (pinfunction "GND_118") (pintype "bidirectional"))
      (node (ref "U2") (pin "119") (pinfunction "GND_119") (pintype "bidirectional"))
      (node (ref "U2") (pin "12") (pinfunction "GND_12") (pintype "bidirectional"))
      (node (ref "U2") (pin "120") (pinfunction "GND_120") (pintype "bidirectional"))
      (node (ref "U2") (pin "15") (pinfunction "GND_15") (pintype "bidirectional"))
      (node (ref "U2") (pin "16") (pinfunction "GND_16") (pintype "bidirectional"))
      (node (ref "U2") (pin "17") (pinfunction "GND_17") (pintype "bidirectional"))
      (node (ref "U2") (pin "18") (pinfunction "GND_18") (pintype "bidirectional"))
      (node (ref "U2") (pin "19") (pinfunction "GND_19") (pintype "bidirectional"))
      (node (ref "U2") (pin "2") (pinfunction "GND_2") (pintype "bidirectional"))
      (node (ref "U2") (pin "20") (pinfunction "GND_20") (pintype "bidirectional"))
      (node (ref "U2") (pin "21") (pinfunction "GND_21") (pintype "bidirectional"))
      (node (ref "U2") (pin "22") (pinfunction "GND_22") (pintype "bidirectional"))
      (node (ref "U2") (pin "23") (pinfunction "GND_23") (pintype "bidirectional"))
      (node (ref "U2") (pin "24") (pinfunction "GND_24") (pintype "bidirectional"))
      (node (ref "U2") (pin "25") (pinfunction "GND_25") (pintype "bidirectional"))
      (node (ref "U2") (pin "26") (pinfunction "GND_26") (pintype "bidirectional"))
      (node (ref "U2") (pin "27") (pinfunction "GND_27") (pintype "bidirectional"))
      (node (ref "U2") (pin "28") (pinfunction "GND_28") (pintype "bidirectional"))
      (node (ref "U2") (pin "29") (pinfunction "GND_29") (pintype "bidirectional"))
      (node (ref "U2") (pin "3") (pinfunction "GND_3") (pintype "bidirectional"))
      (node (ref "U2") (pin "30") (pinfunction "GND_30") (pintype "bidirectional"))
      (node (ref "U2") (pin "31") (pinfunction "GND_31") (pintype "bidirectional"))
      (node (ref "U2") (pin "32") (pinfunction "GND_32") (pintype "bidirectional"))
      (node (ref "U2") (pin "33") (pinfunction "GND_33") (pintype "bidirectional"))
      (node (ref "U2") (pin "34") (pinfunction "GND_34") (pintype "bidirectional"))
      (node (ref "U2") (pin "35") (pinfunction "GND_35") (pintype "bidirectional"))
      (node (ref "U2") (pin "36") (pinfunction "GND_36") (pintype "bidirectional"))
      (node (ref "U2") (pin "38") (pinfunction "GND_38") (pintype "bidirectional"))
      (node (ref "U2") (pin "39") (pinfunction "GND_39") (pintype "bidirectional"))
      (node (ref "U2") (pin "40") (pinfunction "GND_40") (pintype "bidirectional"))
      (node (ref "U2") (pin "41") (pinfunction "GND_41") (pintype "bidirectional"))
      (node (ref "U2") (pin "42") (pinfunction "GND_42") (pintype "bidirectional"))
      (node (ref "U2") (pin "43") (pinfunction "GND_43") (pintype "bidirectional"))
      (node (ref "U2") (pin "44") (pinfunction "GND_44") (pintype "bidirectional"))
      (node (ref "U2") (pin "45") (pinfunction "GND_45") (pintype "bidirectional"))
      (node (ref "U2") (pin "46") (pinfunction "GND_46") (pintype "bidirectional"))
      (node (ref "U2") (pin "47") (pinfunction "GND_47") (pintype "bidirectional"))
      (node (ref "U2") (pin "48") (pinfunction "GND_48") (pintype "bidirectional"))
      (node (ref "U2") (pin "51") (pinfunction "GND_51") (pintype "bidirectional"))
      (node (ref "U2") (pin "55") (pinfunction "GND_55") (pintype "bidirectional"))
      (node (ref "U2") (pin "6") (pinfunction "GND_6") (pintype "bidirectional"))
      (node (ref "U2") (pin "68") (pinfunction "GND_68") (pintype "bidirectional"))
      (node (ref "U2") (pin "69") (pinfunction "GND_69") (pintype "bidirectional"))
      (node (ref "U2") (pin "70") (pinfunction "GND_70") (pintype "bidirectional"))
      (node (ref "U2") (pin "71") (pinfunction "GND_71") (pintype "bidirectional"))
      (node (ref "U2") (pin "72") (pinfunction "GND_72") (pintype "bidirectional"))
      (node (ref "U2") (pin "73") (pinfunction "GND_73") (pintype "bidirectional"))
      (node (ref "U2") (pin "74") (pinfunction "GND_74") (pintype "bidirectional"))
      (node (ref "U2") (pin "75") (pinfunction "GND_75") (pintype "bidirectional"))
      (node (ref "U2") (pin "79") (pinfunction "GND_79") (pintype "bidirectional"))
      (node (ref "U2") (pin "80") (pinfunction "GND_80") (pintype "bidirectional"))
      (node (ref "U2") (pin "81") (pinfunction "GND_81") (pintype "bidirectional"))
      (node (ref "U2") (pin "86") (pinfunction "GND_86") (pintype "bidirectional"))
      (node (ref "U2") (pin "87") (pinfunction "GND_87") (pintype "bidirectional"))
      (node (ref "U2") (pin "88") (pinfunction "GND_88") (pintype "bidirectional"))
      (node (ref "U2") (pin "89") (pinfunction "GND_89") (pintype "bidirectional"))
      (node (ref "U2") (pin "9") (pinfunction "GND_9") (pintype "bidirectional"))
      (node (ref "U2") (pin "90") (pinfunction "GND_90") (pintype "bidirectional"))
      (node (ref "U2") (pin "91") (pinfunction "GND_91") (pintype "bidirectional"))
      (node (ref "U2") (pin "92") (pinfunction "GND_92") (pintype "bidirectional"))
      (node (ref "U2") (pin "93") (pinfunction "GND_93") (pintype "bidirectional"))
      (node (ref "U2") (pin "94") (pinfunction "GND_94") (pintype "bidirectional"))
      (node (ref "U2") (pin "95") (pinfunction "GND_95") (pintype "bidirectional"))
      (node (ref "U2") (pin "96") (pinfunction "GND_96") (pintype "bidirectional"))
      (node (ref "U2") (pin "97") (pinfunction "GND_97") (pintype "bidirectional"))
      (node (ref "U2") (pin "98") (pinfunction "GND_98") (pintype "bidirectional"))
      (node (ref "U2") (pin "99") (pinfunction "GND_99") (pintype "bidirectional"))
      (node (ref "U7") (pin "3") (pinfunction "SGND_3") (pintype "power_in"))
      (node (ref "U7") (pin "5") (pinfunction "PGND_5") (pintype "power_in"))
      (node (ref "U7") (pin "6") (pinfunction "PGND_6") (pintype "power_in"))
      (node (ref "U7") (pin "P$1") (pinfunction "PGND_P$1") (pintype "power_in"))
      (node (ref "X1") (pin "1") (pinfunction "1_1") (pintype "passive"))
      (node (ref "X1") (pin "103") (pinfunction "1_103") (pintype "passive"))
      (node (ref "X1") (pin "104") (pinfunction "1_104") (pintype "passive"))
      (node (ref "X1") (pin "109") (pinfunction "1_109") (pintype "passive"))
      (node (ref "X1") (pin "110") (pinfunction "1_110") (pintype "passive"))
      (node (ref "X1") (pin "115") (pinfunction "1_115") (pintype "passive"))
      (node (ref "X1") (pin "116") (pinfunction "1_116") (pintype "passive"))
      (node (ref "X1") (pin "121") (pinfunction "1_121") (pintype "passive"))
      (node (ref "X1") (pin "122") (pinfunction "1_122") (pintype "passive"))
      (node (ref "X1") (pin "127") (pinfunction "1_127") (pintype "passive"))
      (node (ref "X1") (pin "128") (pinfunction "1_128") (pintype "passive"))
      (node (ref "X1") (pin "13") (pinfunction "1_13") (pintype "passive"))
      (node (ref "X1") (pin "133") (pinfunction "1_133") (pintype "passive"))
      (node (ref "X1") (pin "134") (pinfunction "1_134") (pintype "passive"))
      (node (ref "X1") (pin "139") (pinfunction "1_139") (pintype "passive"))
      (node (ref "X1") (pin "14") (pinfunction "1_14") (pintype "passive"))
      (node (ref "X1") (pin "140") (pinfunction "1_140") (pintype "passive"))
      (node (ref "X1") (pin "145") (pinfunction "1_145") (pintype "passive"))
      (node (ref "X1") (pin "146") (pinfunction "1_146") (pintype "passive"))
      (node (ref "X1") (pin "151") (pinfunction "1_151") (pintype "passive"))
      (node (ref "X1") (pin "152") (pinfunction "1_152") (pintype "passive"))
      (node (ref "X1") (pin "157") (pinfunction "1_157") (pintype "passive"))
      (node (ref "X1") (pin "158") (pinfunction "1_158") (pintype "passive"))
      (node (ref "X1") (pin "163") (pinfunction "1_163") (pintype "passive"))
      (node (ref "X1") (pin "164") (pinfunction "1_164") (pintype "passive"))
      (node (ref "X1") (pin "170") (pinfunction "1_170") (pintype "passive"))
      (node (ref "X1") (pin "181") (pinfunction "1_181") (pintype "passive"))
      (node (ref "X1") (pin "182") (pinfunction "1_182") (pintype "passive"))
      (node (ref "X1") (pin "187") (pinfunction "1_187") (pintype "passive"))
      (node (ref "X1") (pin "188") (pinfunction "1_188") (pintype "passive"))
      (node (ref "X1") (pin "19") (pinfunction "1_19") (pintype "passive"))
      (node (ref "X1") (pin "195") (pinfunction "1_195") (pintype "passive"))
      (node (ref "X1") (pin "196") (pinfunction "1_196") (pintype "passive"))
      (node (ref "X1") (pin "20") (pinfunction "1_20") (pintype "passive"))
      (node (ref "X1") (pin "25") (pinfunction "1_25") (pintype "passive"))
      (node (ref "X1") (pin "26") (pinfunction "1_26") (pintype "passive"))
      (node (ref "X1") (pin "31") (pinfunction "1_31") (pintype "passive"))
      (node (ref "X1") (pin "32") (pinfunction "1_32") (pintype "passive"))
      (node (ref "X1") (pin "37") (pinfunction "1_37") (pintype "passive"))
      (node (ref "X1") (pin "38") (pinfunction "1_38") (pintype "passive"))
      (node (ref "X1") (pin "43") (pinfunction "1_43") (pintype "passive"))
      (node (ref "X1") (pin "44") (pinfunction "1_44") (pintype "passive"))
      (node (ref "X1") (pin "49") (pinfunction "1_49") (pintype "passive"))
      (node (ref "X1") (pin "50") (pinfunction "1_50") (pintype "passive"))
      (node (ref "X1") (pin "55") (pinfunction "1_55") (pintype "passive"))
      (node (ref "X1") (pin "56") (pinfunction "1_56") (pintype "passive"))
      (node (ref "X1") (pin "61") (pinfunction "1_61") (pintype "passive"))
      (node (ref "X1") (pin "62") (pinfunction "1_62") (pintype "passive"))
      (node (ref "X1") (pin "67") (pinfunction "1_67") (pintype "passive"))
      (node (ref "X1") (pin "68") (pinfunction "1_68") (pintype "passive"))
      (node (ref "X1") (pin "7") (pinfunction "1_7") (pintype "passive"))
      (node (ref "X1") (pin "73") (pinfunction "1_73") (pintype "passive"))
      (node (ref "X1") (pin "74") (pinfunction "1_74") (pintype "passive"))
      (node (ref "X1") (pin "79") (pinfunction "1_79") (pintype "passive"))
      (node (ref "X1") (pin "8") (pinfunction "1_8") (pintype "passive"))
      (node (ref "X1") (pin "80") (pinfunction "1_80") (pintype "passive"))
      (node (ref "X1") (pin "85") (pinfunction "1_85") (pintype "passive"))
      (node (ref "X1") (pin "86") (pinfunction "1_86") (pintype "passive"))
      (node (ref "X1") (pin "91") (pinfunction "1_91") (pintype "passive"))
      (node (ref "X1") (pin "92") (pinfunction "1_92") (pintype "passive"))
      (node (ref "X1") (pin "97") (pinfunction "1_97") (pintype "passive"))
      (node (ref "X1") (pin "98") (pinfunction "1_98") (pintype "passive"))
      (node (ref "Y1") (pin "2") (pinfunction "2_2") (pintype "passive"))
      (node (ref "Y1") (pin "4") (pinfunction "4_4") (pintype "passive"))
    )
    (net (code "84") (name "GPIO0$1") (class "Default")
      (node (ref "J1") (pin "36") (pinfunction "36_36") (pintype "passive"))
      (node (ref "X1") (pin "3") (pinfunction "1_3") (pintype "passive"))
    )
    (net (code "85") (name "GPIO0-27_VDD$1") (class "Default")
      (node (ref "X1") (pin "39") (pinfunction "1_39") (pintype "passive"))
      (node (ref "X1") (pin "40") (pinfunction "1_40") (pintype "passive"))
    )
    (net (code "86") (name "GPIO1$1") (class "Default")
      (node (ref "J1") (pin "35") (pinfunction "35_35") (pintype "passive"))
      (node (ref "X1") (pin "5") (pinfunction "1_5") (pintype "passive"))
    )
    (net (code "87") (name "GPIO2$1") (class "Default")
      (node (ref "J1") (pin "58") (pinfunction "58_58") (pintype "passive"))
      (node (ref "R7") (pin "1") (pinfunction "1_1") (pintype "passive"))
      (node (ref "U1") (pin "P20") (pinfunction "SDA_P20") (pintype "bidirectional"))
      (node (ref "X1") (pin "9") (pinfunction "1_9") (pintype "passive"))
    )
    (net (code "88") (name "GPIO3$1") (class "Default")
      (node (ref "J1") (pin "56") (pinfunction "56_56") (pintype "passive"))
      (node (ref "R8") (pin "1") (pinfunction "1_1") (pintype "passive"))
      (node (ref "U1") (pin "P19") (pinfunction "SCL_P19") (pintype "bidirectional"))
      (node (ref "X1") (pin "11") (pinfunction "1_11") (pintype "passive"))
    )
    (net (code "89") (name "GPIO4$1") (class "Default")
      (node (ref "J1") (pin "54") (pinfunction "54_54") (pintype "passive"))
      (node (ref "X1") (pin "15") (pinfunction "1_15") (pintype "passive"))
    )
    (net (code "90") (name "GPIO5$1") (class "Default")
      (node (ref "J1") (pin "34") (pinfunction "34_34") (pintype "passive"))
      (node (ref "X1") (pin "17") (pinfunction "1_17") (pintype "passive"))
    )
    (net (code "91") (name "GPIO6$1") (class "Default")
      (node (ref "J1") (pin "30") (pinfunction "30_30") (pintype "passive"))
      (node (ref "X1") (pin "21") (pinfunction "1_21") (pintype "passive"))
    )
    (net (code "92") (name "GPIO7$1") (class "Default")
      (node (ref "J1") (pin "37") (pinfunction "37_37") (pintype "passive"))
      (node (ref "X1") (pin "23") (pinfunction "1_23") (pintype "passive"))
    )
    (net (code "93") (name "GPIO8$1") (class "Default")
      (node (ref "J1") (pin "39") (pinfunction "39_39") (pintype "passive"))
      (node (ref "X1") (pin "27") (pinfunction "1_27") (pintype "passive"))
    )
    (net (code "94") (name "GPIO9$1") (class "Default")
      (node (ref "J1") (pin "40") (pinfunction "40_40") (pintype "passive"))
      (node (ref "X1") (pin "29") (pinfunction "1_29") (pintype "passive"))
    )
    (net (code "95") (name "GPIO10$1") (class "Default")
      (node (ref "J1") (pin "44") (pinfunction "44_44") (pintype "passive"))
      (node (ref "X1") (pin "33") (pinfunction "1_33") (pintype "passive"))
    )
    (net (code "96") (name "GPIO11$1") (class "Default")
      (node (ref "J1") (pin "38") (pinfunction "38_38") (pintype "passive"))
      (node (ref "X1") (pin "35") (pinfunction "1_35") (pintype "passive"))
    )
    (net (code "97") (name "GPIO12$1") (class "Default")
      (node (ref "J1") (pin "31") (pinfunction "31_31") (pintype "passive"))
      (node (ref "X1") (pin "45") (pinfunction "1_45") (pintype "passive"))
    )
    (net (code "98") (name "GPIO13$1") (class "Default")
      (node (ref "J1") (pin "28") (pinfunction "28_28") (pintype "passive"))
      (node (ref "X1") (pin "47") (pinfunction "1_47") (pintype "passive"))
    )
    (net (code "99") (name "GPIO14$1") (class "Default")
      (node (ref "J1") (pin "55") (pinfunction "55_55") (pintype "passive"))
      (node (ref "X1") (pin "51") (pinfunction "1_51") (pintype "passive"))
    )
    (net (code "100") (name "GPIO15$1") (class "Default")
      (node (ref "J1") (pin "51") (pinfunction "51_51") (pintype "passive"))
      (node (ref "X1") (pin "53") (pinfunction "1_53") (pintype "passive"))
    )
    (net (code "101") (name "GPIO16$1") (class "Default")
      (node (ref "J1") (pin "29") (pinfunction "29_29") (pintype "passive"))
      (node (ref "X1") (pin "57") (pinfunction "1_57") (pintype "passive"))
    )
    (net (code "102") (name "GPIO17$1") (class "Default")
      (node (ref "J1") (pin "50") (pinfunction "50_50") (pintype "passive"))
      (node (ref "X1") (pin "59") (pinfunction "1_59") (pintype "passive"))
    )
    (net (code "103") (name "GPIO18$1") (class "Default")
      (node (ref "J1") (pin "49") (pinfunction "49_49") (pintype "passive"))
      (node (ref "X1") (pin "63") (pinfunction "1_63") (pintype "passive"))
    )
    (net (code "104") (name "GPIO19$1") (class "Default")
      (node (ref "J1") (pin "26") (pinfunction "26_26") (pintype "passive"))
      (node (ref "X1") (pin "65") (pinfunction "1_65") (pintype "passive"))
    )
    (net (code "105") (name "GPIO20$1") (class "Default")
      (node (ref "J1") (pin "27") (pinfunction "27_27") (pintype "passive"))
      (node (ref "X1") (pin "69") (pinfunction "1_69") (pintype "passive"))
    )
    (net (code "106") (name "GPIO21$1") (class "Default")
      (node (ref "J1") (pin "25") (pinfunction "25_25") (pintype "passive"))
      (node (ref "X1") (pin "71") (pinfunction "1_71") (pintype "passive"))
    )
    (net (code "107") (name "GPIO22$1") (class "Default")
      (node (ref "J1") (pin "46") (pinfunction "46_46") (pintype "passive"))
      (node (ref "X1") (pin "75") (pinfunction "1_75") (pintype "passive"))
    )
    (net (code "108") (name "GPIO23$1") (class "Default")
      (node (ref "J1") (pin "47") (pinfunction "47_47") (pintype "passive"))
      (node (ref "X1") (pin "77") (pinfunction "1_77") (pintype "passive"))
    )
    (net (code "109") (name "GPIO24$1") (class "Default")
      (node (ref "J1") (pin "45") (pinfunction "45_45") (pintype "passive"))
      (node (ref "X1") (pin "81") (pinfunction "1_81") (pintype "passive"))
    )
    (net (code "110") (name "GPIO25$1") (class "Default")
      (node (ref "J1") (pin "41") (pinfunction "41_41") (pintype "passive"))
      (node (ref "X1") (pin "83") (pinfunction "1_83") (pintype "passive"))
    )
    (net (code "111") (name "GPIO26$1") (class "Default")
      (node (ref "J1") (pin "24") (pinfunction "24_24") (pintype "passive"))
      (node (ref "X1") (pin "87") (pinfunction "1_87") (pintype "passive"))
    )
    (net (code "112") (name "GPIO27$1") (class "Default")
      (node (ref "J1") (pin "48") (pinfunction "48_48") (pintype "passive"))
      (node (ref "X1") (pin "89") (pinfunction "1_89") (pintype "passive"))
    )
    (net (code "113") (name "GPIO28$1") (class "Default")
      (node (ref "U1") (pin "P1") (pinfunction "P00_P1") (pintype "bidirectional"))
      (node (ref "X1") (pin "28") (pinfunction "1_28") (pintype "passive"))
    )
    (net (code "114") (name "GPIO28-45_VDD$1") (class "Default")
      (node (ref "X1") (pin "41") (pinfunction "1_41") (pintype "passive"))
      (node (ref "X1") (pin "42") (pinfunction "1_42") (pintype "passive"))
    )
    (net (code "115") (name "GPIO29$1") (class "Default")
      (node (ref "U1") (pin "P2") (pinfunction "P01_P2") (pintype "bidirectional"))
      (node (ref "X1") (pin "30") (pinfunction "1_30") (pintype "passive"))
    )
    (net (code "116") (name "GPIO30$1") (class "Default")
      (node (ref "U1") (pin "P3") (pinfunction "P02_P3") (pintype "bidirectional"))
      (node (ref "X1") (pin "34") (pinfunction "1_34") (pintype "passive"))
    )
    (net (code "117") (name "GPIO31$1") (class "Default")
      (node (ref "U1") (pin "P4") (pinfunction "P03_P4") (pintype "bidirectional"))
      (node (ref "X1") (pin "36") (pinfunction "1_36") (pintype "passive"))
    )
    (net (code "118") (name "GPIO32$1") (class "Default")
      (node (ref "U1") (pin "P5") (pinfunction "P04_P5") (pintype "bidirectional"))
      (node (ref "X1") (pin "46") (pinfunction "1_46") (pintype "passive"))
    )
    (net (code "119") (name "GPIO33$1") (class "Default")
      (node (ref "U1") (pin "P6") (pinfunction "P05_P6") (pintype "bidirectional"))
      (node (ref "X1") (pin "48") (pinfunction "1_48") (pintype "passive"))
    )
    (net (code "120") (name "GPIO34$1") (class "Default")
      (node (ref "U1") (pin "P7") (pinfunction "P06_P7") (pintype "bidirectional"))
      (node (ref "X1") (pin "52") (pinfunction "1_52") (pintype "passive"))
    )
    (net (code "121") (name "GPIO35$1") (class "Default")
      (node (ref "U1") (pin "P8") (pinfunction "P07_P8") (pintype "bidirectional"))
      (node (ref "X1") (pin "54") (pinfunction "1_54") (pintype "passive"))
    )
    (net (code "122") (name "GPIO36$1") (class "Default")
      (node (ref "U1") (pin "P10") (pinfunction "P10_P10") (pintype "bidirectional"))
      (node (ref "X1") (pin "58") (pinfunction "1_58") (pintype "passive"))
    )
    (net (code "123") (name "GPIO37$1") (class "Default")
      (node (ref "U1") (pin "P11") (pinfunction "P11_P11") (pintype "bidirectional"))
      (node (ref "X1") (pin "60") (pinfunction "1_60") (pintype "passive"))
    )
    (net (code "124") (name "GPIO38$1") (class "Default")
      (node (ref "U1") (pin "P12") (pinfunction "P12_P12") (pintype "bidirectional"))
      (node (ref "X1") (pin "64") (pinfunction "1_64") (pintype "passive"))
    )
    (net (code "125") (name "GPIO39$1") (class "Default")
      (node (ref "U1") (pin "P13") (pinfunction "P13_P13") (pintype "bidirectional"))
      (node (ref "X1") (pin "66") (pinfunction "1_66") (pintype "passive"))
    )
    (net (code "126") (name "GPIO40$1") (class "Default")
      (node (ref "U1") (pin "P14") (pinfunction "P14_P14") (pintype "bidirectional"))
      (node (ref "X1") (pin "70") (pinfunction "1_70") (pintype "passive"))
    )
    (net (code "127") (name "GPIO41$1") (class "Default")
      (node (ref "U1") (pin "P15") (pinfunction "P15_P15") (pintype "bidirectional"))
      (node (ref "X1") (pin "72") (pinfunction "1_72") (pintype "passive"))
    )
    (net (code "128") (name "GPIO42$1") (class "Default")
      (node (ref "U1") (pin "P16") (pinfunction "P16_P16") (pintype "bidirectional"))
      (node (ref "X1") (pin "76") (pinfunction "1_76") (pintype "passive"))
    )
    (net (code "129") (name "GPIO43$1") (class "Default")
      (node (ref "U1") (pin "P17") (pinfunction "P17_P17") (pintype "bidirectional"))
      (node (ref "X1") (pin "78") (pinfunction "1_78") (pintype "passive"))
    )
    (net (code "130") (name "GPIO_INT") (class "Default")
      (node (ref "R2") (pin "1") (pinfunction "1_1") (pintype "passive"))
      (node (ref "U1") (pin "P22") (pinfunction "~{INT}_P22") (pintype "bidirectional"))
    )
    (net (code "131") (name "GPIO_VREF$2") (class "Default")
      (node (ref "J1") (pin "78") (pinfunction "78_78") (pintype "passive"))
      (node (ref "R79") (pin "2") (pinfunction "2_2") (pintype "passive"))
    )
    (net (code "132") (name "GPIO_~{RESET}") (class "Default")
      (node (ref "R1") (pin "1") (pinfunction "1_1") (pintype "passive"))
      (node (ref "U1") (pin "P24") (pinfunction "~{RESET}_P24") (pintype "bidirectional"))
    )
    (net (code "133") (name "HDMI1_CEC") (class "Default")
      (node (ref "J2") (pin "49") (pinfunction "49_49") (pintype "passive"))
    )
    (net (code "134") (name "HDMI1_CLK_N") (class "Default")
      (node (ref "J2") (pin "66") (pinfunction "66_66") (pintype "passive"))
    )
    (net (code "135") (name "HDMI1_CLK_P") (class "Default")
      (node (ref "J2") (pin "64") (pinfunction "64_64") (pintype "passive"))
    )
    (net (code "136") (name "HDMI1_HPG") (class "Default")
      (node (ref "J2") (pin "43") (pinfunction "43_43") (pintype "passive"))
    )
    (net (code "137") (name "HDMI1_SCL") (class "Default")
      (node (ref "J2") (pin "47") (pinfunction "47_47") (pintype "passive"))
    )
    (net (code "138") (name "HDMI1_SDA") (class "Default")
      (node (ref "J2") (pin "45") (pinfunction "45_45") (pintype "passive"))
    )
    (net (code "139") (name "HDMI1_TX0_N") (class "Default")
      (node (ref "J2") (pin "60") (pinfunction "60_60") (pintype "passive"))
    )
    (net (code "140") (name "HDMI1_TX0_P") (class "Default")
      (node (ref "J2") (pin "58") (pinfunction "58_58") (pintype "passive"))
    )
    (net (code "141") (name "HDMI1_TX1_N") (class "Default")
      (node (ref "J2") (pin "54") (pinfunction "54_54") (pintype "passive"))
    )
    (net (code "142") (name "HDMI1_TX1_P") (class "Default")
      (node (ref "J2") (pin "52") (pinfunction "52_52") (pintype "passive"))
    )
    (net (code "143") (name "HDMI1_TX2_N") (class "Default")
      (node (ref "J2") (pin "48") (pinfunction "48_48") (pintype "passive"))
    )
    (net (code "144") (name "HDMI1_TX2_P") (class "Default")
      (node (ref "J2") (pin "46") (pinfunction "46_46") (pintype "passive"))
    )
    (net (code "145") (name "HDMI_HPD_N_1V8$1") (class "Default")
      (node (ref "Q2") (pin "1") (pinfunction "G_1") (pintype "passive"))
      (node (ref "X1") (pin "88") (pinfunction "1_88") (pintype "passive"))
    )
    (net (code "146") (name "Net-(C58-Pad2)") (class "Default")
      (node (ref "C58") (pin "2") (pinfunction "2_2") (pintype "passive"))
      (node (ref "R76") (pin "2") (pinfunction "2_2") (pintype "passive"))
    )
    (net (code "147") (name "Net-(C60-Pad1)") (class "Default")
      (node (ref "C60") (pin "1") (pinfunction "1_1") (pintype "passive"))
      (node (ref "R78") (pin "1") (pinfunction "1_1") (pintype "passive"))
    )
    (net (code "148") (name "Net-(Q3-G)") (class "Default")
      (node (ref "Q3") (pin "1") (pinfunction "G_1") (pintype "passive"))
      (node (ref "Q4") (pin "3") (pinfunction "D_3") (pintype "passive"))
    )
    (net (code "149") (name "Net-(U2-PGOOD4)") (class "Default")
      (node (ref "R35") (pin "2") (pinfunction "2_2") (pintype "passive"))
      (node (ref "U2") (pin "37") (pinfunction "PGOOD4_37") (pintype "bidirectional"))
    )
    (net (code "150") (name "Net-(U2-USB2_D_N)") (class "Default")
      (node (ref "R13") (pin "2") (pinfunction "2_2") (pintype "passive"))
      (node (ref "U2") (pin "14") (pinfunction "USB2_D_N_14") (pintype "bidirectional"))
    )
    (net (code "151") (name "Net-(U2-USB2_D_P)") (class "Default")
      (node (ref "R11") (pin "2") (pinfunction "2_2") (pintype "passive"))
      (node (ref "U2") (pin "13") (pinfunction "USB2_D_P_13") (pintype "bidirectional"))
    )
    (net (code "152") (name "Net-(U2-USB_SEL)") (class "Default")
      (node (ref "R12") (pin "2") (pinfunction "2_2") (pintype "passive"))
      (node (ref "U2") (pin "83") (pinfunction "USB_SEL_83") (pintype "bidirectional"))
    )
    (net (code "153") (name "Net-(U7-BURST)") (class "Default")
      (node (ref "C10") (pin "1") (pinfunction "1_1") (pintype "passive"))
      (node (ref "R74") (pin "2") (pinfunction "2_2") (pintype "passive"))
      (node (ref "U7") (pin "2") (pinfunction "BURST_2") (pintype "input"))
    )
    (net (code "154") (name "Net-(U7-FB)") (class "Default")
      (node (ref "C55") (pin "2") (pinfunction "2_2") (pintype "passive"))
      (node (ref "C60") (pin "2") (pinfunction "2_2") (pintype "passive"))
      (node (ref "R75") (pin "1") (pinfunction "1_1") (pintype "passive"))
      (node (ref "R76") (pin "1") (pinfunction "1_1") (pintype "passive"))
      (node (ref "R77") (pin "2") (pinfunction "2_2") (pintype "passive"))
      (node (ref "U7") (pin "13") (pinfunction "FB_13") (pintype "output"))
    )
    (net (code "155") (name "Net-(U7-RT)") (class "Default")
      (node (ref "R6") (pin "2") (pinfunction "2_2") (pintype "passive"))
      (node (ref "U7") (pin "1") (pinfunction "RT_1") (pintype "input"))
    )
    (net (code "156") (name "Net-(U7-SW1)") (class "Default")
      (node (ref "L4") (pin "1") (pinfunction "1_1") (pintype "passive"))
      (node (ref "U7") (pin "4") (pinfunction "SW1_4") (pintype "input"))
    )
    (net (code "157") (name "Net-(U7-SW2)") (class "Default")
      (node (ref "D2") (pin "A") (pinfunction "A_A") (pintype "passive"))
      (node (ref "L4") (pin "2") (pinfunction "2_2") (pintype "passive"))
      (node (ref "U7") (pin "7") (pinfunction "SW2_7") (pintype "input"))
    )
    (net (code "158") (name "Net-(U7-VC)") (class "Default")
      (node (ref "C55") (pin "1") (pinfunction "1_1") (pintype "passive"))
      (node (ref "R78") (pin "2") (pinfunction "2_2") (pintype "passive"))
      (node (ref "U7") (pin "14") (pinfunction "VC_14") (pintype "input"))
    )
    (net (code "159") (name "Net-(U11-CRFILT)") (class "Default")
      (node (ref "C13") (pin "1") (pinfunction "1_1") (pintype "passive"))
      (node (ref "U11") (pin "P10") (pinfunction "CRFILT_P10") (pintype "passive"))
    )
    (net (code "160") (name "Net-(U11-RBIAS)") (class "Default")
      (node (ref "R17") (pin "2") (pinfunction "2_2") (pintype "passive"))
      (node (ref "U11") (pin "P24") (pinfunction "RBIAS_P24") (pintype "passive"))
    )
    (net (code "161") (name "Net-(U11-RESET_N)") (class "Default")
      (node (ref "R15") (pin "1") (pinfunction "1_1") (pintype "passive"))
      (node (ref "U11") (pin "P15") (pinfunction "RESET_N_P15") (pintype "passive"))
    )
    (net (code "162") (name "Net-(U11-SCL{slash}CFG_SEL0)") (class "Default")
      (node (ref "R19") (pin "2") (pinfunction "2_2") (pintype "passive"))
      (node (ref "U11") (pin "P14") (pinfunction "SCL/CFG_SEL0_P14") (pintype "passive"))
    )
    (net (code "163") (name "Net-(U11-SDA{slash}NON_REM1)") (class "Default")
      (node (ref "R18") (pin "1") (pinfunction "1_1") (pintype "passive"))
      (node (ref "U11") (pin "P13") (pinfunction "SDA/NON_REM1_P13") (pintype "passive"))
    )
    (net (code "164") (name "Net-(U11-SUSP_IND{slash}NON_REM0)") (class "Default")
      (node (ref "R20") (pin "2") (pinfunction "2_2") (pintype "passive"))
      (node (ref "U11") (pin "P17") (pinfunction "SUSP_IND/NON_REM0_P17") (pintype "passive"))
    )
    (net (code "165") (name "Net-(U11-VBUS_DET)") (class "Default")
      (node (ref "R14") (pin "2") (pinfunction "2_2") (pintype "passive"))
      (node (ref "U11") (pin "P16") (pinfunction "VBUS_DET_P16") (pintype "passive"))
    )
    (net (code "166") (name "PCIE_CLK_N") (class "Default")
      (node (ref "J2") (pin "12") (pinfunction "12_12") (pintype "passive"))
      (node (ref "R26") (pin "1") (pinfunction "1_1") (pintype "passive"))
    )
    (net (code "167") (name "PCIE_CLK_P") (class "Default")
      (node (ref "J2") (pin "10") (pinfunction "10_10") (pintype "passive"))
      (node (ref "R25") (pin "1") (pinfunction "1_1") (pintype "passive"))
    )
    (net (code "168") (name "PCIE_CLK__N") (class "Default")
      (node (ref "X1") (pin "132") (pinfunction "1_132") (pintype "passive"))
    )
    (net (code "169") (name "PCIE_CLK__P") (class "Default")
      (node (ref "X1") (pin "130") (pinfunction "1_130") (pintype "passive"))
    )
    (net (code "170") (name "PCIE_RX_N") (class "Default")
      (node (ref "J2") (pin "18") (pinfunction "18_18") (pintype "passive"))
      (node (ref "R22") (pin "1") (pinfunction "1_1") (pintype "passive"))
    )
    (net (code "171") (name "PCIE_RX_P") (class "Default")
      (node (ref "J2") (pin "16") (pinfunction "16_16") (pintype "passive"))
      (node (ref "R21") (pin "1") (pinfunction "1_1") (pintype "passive"))
    )
    (net (code "172") (name "PCIE_RX__N") (class "Default")
      (node (ref "X1") (pin "156") (pinfunction "1_156") (pintype "passive"))
    )
    (net (code "173") (name "PCIE_RX__P") (class "Default")
      (node (ref "X1") (pin "154") (pinfunction "1_154") (pintype "passive"))
    )
    (net (code "174") (name "PCIE_R_X_N") (class "Default")
      (node (ref "R22") (pin "2") (pinfunction "2_2") (pintype "passive"))
      (node (ref "U2") (pin "4") (pinfunction "PCIE_TX_N_4") (pintype "bidirectional"))
    )
    (net (code "175") (name "PCIE_R_X_P") (class "Default")
      (node (ref "R21") (pin "2") (pinfunction "2_2") (pintype "passive"))
      (node (ref "U2") (pin "5") (pinfunction "PCIE_TX_P_5") (pintype "bidirectional"))
    )
    (net (code "176") (name "PCIE_TX_N") (class "Default")
      (node (ref "J2") (pin "24") (pinfunction "24_24") (pintype "passive"))
      (node (ref "R24") (pin "1") (pinfunction "1_1") (pintype "passive"))
    )
    (net (code "177") (name "PCIE_TX_P") (class "Default")
      (node (ref "J2") (pin "22") (pinfunction "22_22") (pintype "passive"))
      (node (ref "R23") (pin "1") (pinfunction "1_1") (pintype "passive"))
    )
    (net (code "178") (name "PCIE_TX__N") (class "Default")
      (node (ref "X1") (pin "162") (pinfunction "1_162") (pintype "passive"))
    )
    (net (code "179") (name "PCIE_TX__P") (class "Default")
      (node (ref "X1") (pin "160") (pinfunction "1_160") (pintype "passive"))
    )
    (net (code "180") (name "PCIE_T_X_N") (class "Default")
      (node (ref "R24") (pin "2") (pinfunction "2_2") (pintype "passive"))
      (node (ref "R32") (pin "1") (pinfunction "1_1") (pintype "passive"))
      (node (ref "U2") (pin "8") (pinfunction "PCIE_RX_N_8") (pintype "bidirectional"))
    )
    (net (code "181") (name "PCIE_T_X_P") (class "Default")
      (node (ref "R23") (pin "2") (pinfunction "2_2") (pintype "passive"))
      (node (ref "R31") (pin "1") (pinfunction "1_1") (pintype "passive"))
      (node (ref "U2") (pin "7") (pinfunction "PCIE_RX_P_7") (pintype "bidirectional"))
    )
    (net (code "182") (name "PCIE__CLK_N") (class "Default")
      (node (ref "R26") (pin "2") (pinfunction "2_2") (pintype "passive"))
      (node (ref "R34") (pin "1") (pinfunction "1_1") (pintype "passive"))
      (node (ref "U2") (pin "10") (pinfunction "PCIE_REFCLK_N_10") (pintype "bidirectional"))
    )
    (net (code "183") (name "PCIE__CLK_P") (class "Default")
      (node (ref "R25") (pin "2") (pinfunction "2_2") (pintype "passive"))
      (node (ref "R33") (pin "1") (pinfunction "1_1") (pintype "passive"))
      (node (ref "U2") (pin "11") (pinfunction "PCIE_REFCLK_P_11") (pintype "bidirectional"))
    )
    (net (code "184") (name "PCIE__~{CLKREQ}") (class "Default")
      (node (ref "R27") (pin "2") (pinfunction "2_2") (pintype "passive"))
      (node (ref "U2") (pin "78") (pinfunction "~{CLKREQ}_78") (pintype "bidirectional"))
    )
    (net (code "185") (name "PCIE_~{CLKREQ_}") (class "Default")
      (node (ref "X1") (pin "124") (pinfunction "1_124") (pintype "passive"))
    )
    (net (code "186") (name "PCIE_~{CLKREQ}") (class "Default")
      (node (ref "J2") (pin "2") (pinfunction "2_2") (pintype "passive"))
      (node (ref "R27") (pin "1") (pinfunction "1_1") (pintype "passive"))
    )
    (net (code "187") (name "PCIE_~{RST_}") (class "Default")
      (node (ref "X1") (pin "126") (pinfunction "1_126") (pintype "passive"))
    )
    (net (code "188") (name "PCIE_~{RST}") (class "Default")
      (node (ref "J2") (pin "9") (pinfunction "9_9") (pintype "passive"))
    )
    (net (code "189") (name "PI_LED_~{PWR}") (class "Default")
      (node (ref "J1") (pin "95") (pinfunction "95_95") (pintype "passive"))
    )
    (net (code "190") (name "PI_~{LED_ACT}") (class "Default")
      (node (ref "J1") (pin "21") (pinfunction "21_21") (pintype "passive"))
    )
    (net (code "191") (name "RUN_PG") (class "Default")
      (node (ref "J1") (pin "92") (pinfunction "92_92") (pintype "passive"))
      (node (ref "Q4") (pin "1") (pinfunction "G_1") (pintype "passive"))
      (node (ref "R28") (pin "2") (pinfunction "2_2") (pintype "passive"))
    )
    (net (code "192") (name "RUN__PG") (class "Default")
      (node (ref "R28") (pin "1") (pinfunction "1_1") (pintype "passive"))
      (node (ref "X1") (pin "177") (pinfunction "1_177") (pintype "passive"))
    )
    (net (code "193") (name "SD_CLK") (class "Default")
      (node (ref "J1") (pin "57") (pinfunction "57_57") (pintype "passive"))
    )
    (net (code "194") (name "SD_CMD") (class "Default")
      (node (ref "J1") (pin "62") (pinfunction "62_62") (pintype "passive"))
    )
    (net (code "195") (name "SD_DAT0") (class "Default")
      (node (ref "J1") (pin "63") (pinfunction "63_63") (pintype "passive"))
    )
    (net (code "196") (name "SD_DAT1") (class "Default")
      (node (ref "J1") (pin "67") (pinfunction "67_67") (pintype "passive"))
    )
    (net (code "197") (name "SD_DAT2") (class "Default")
      (node (ref "J1") (pin "69") (pinfunction "69_69") (pintype "passive"))
    )
    (net (code "198") (name "SD_DAT3") (class "Default")
      (node (ref "J1") (pin "61") (pinfunction "61_61") (pintype "passive"))
    )
    (net (code "199") (name "SD_DAT4") (class "Default")
      (node (ref "J1") (pin "68") (pinfunction "68_68") (pintype "passive"))
    )
    (net (code "200") (name "SD_DAT5") (class "Default")
      (node (ref "J1") (pin "64") (pinfunction "64_64") (pintype "passive"))
    )
    (net (code "201") (name "SD_DAT6") (class "Default")
      (node (ref "J1") (pin "72") (pinfunction "72_72") (pintype "passive"))
    )
    (net (code "202") (name "SD_DAT7") (class "Default")
      (node (ref "J1") (pin "70") (pinfunction "70_70") (pintype "passive"))
    )
    (net (code "203") (name "SD_PWR_ON") (class "Default")
      (node (ref "J1") (pin "75") (pinfunction "75_75") (pintype "passive"))
    )
    (net (code "204") (name "SD_VDD_OV") (class "Default")
      (node (ref "J1") (pin "73") (pinfunction "73_73") (pintype "passive"))
    )
    (net (code "205") (name "USB_XTAL1$") (class "Default")
      (node (ref "C12") (pin "1") (pinfunction "1_1") (pintype "passive"))
      (node (ref "R16") (pin "2") (pinfunction "2_2") (pintype "passive"))
      (node (ref "U11") (pin "P22") (pinfunction "XTALIN_P22") (pintype "passive"))
      (node (ref "Y1") (pin "3") (pinfunction "3_3") (pintype "passive"))
    )
    (net (code "206") (name "USB_XTAL2$") (class "Default")
      (node (ref "C11") (pin "1") (pinfunction "1_1") (pintype "passive"))
      (node (ref "R16") (pin "1") (pinfunction "1_1") (pintype "passive"))
      (node (ref "U11") (pin "P21") (pinfunction "XTALOUT_P21") (pintype "passive"))
      (node (ref "Y1") (pin "1") (pinfunction "1_1") (pintype "passive"))
    )
    (net (code "207") (name "VDAC$1") (class "Default")
      (node (ref "X1") (pin "189") (pinfunction "1_189") (pintype "passive"))
      (node (ref "X1") (pin "190") (pinfunction "1_190") (pintype "passive"))
    )
    (net (code "208") (name "VDAC_COMP") (class "Default")
      (node (ref "J2") (pin "11") (pinfunction "11_11") (pintype "passive"))
    )
    (net (code "209") (name "VDD_CORE$1") (class "Default")
      (node (ref "X1") (pin "179") (pinfunction "1_179") (pintype "passive"))
    )
    (net (code "210") (name "unconnected-(J1-Pad76)") (class "Default")
      (node (ref "J1") (pin "76") (pinfunction "76_76") (pintype "passive"))
    )
    (net (code "211") (name "unconnected-(J1-Pad89)") (class "Default")
      (node (ref "J1") (pin "89") (pinfunction "89_89") (pintype "passive"))
    )
    (net (code "212") (name "unconnected-(J1-Pad91)") (class "Default")
      (node (ref "J1") (pin "91") (pinfunction "91_91") (pintype "passive"))
    )
    (net (code "213") (name "unconnected-(J1-Pad97)") (class "Default")
      (node (ref "J1") (pin "97") (pinfunction "97_97") (pintype "passive"))
    )
    (net (code "214") (name "unconnected-(J2-Pad4)") (class "Default")
      (node (ref "J2") (pin "4") (pinfunction "4_4") (pintype "passive"))
    )
    (net (code "215") (name "unconnected-(J2-Pad6)") (class "Default")
      (node (ref "J2") (pin "6") (pinfunction "6_6") (pintype "passive"))
    )
    (net (code "216") (name "unconnected-(U2-INTR-Pad77)") (class "Default")
      (node (ref "U2") (pin "77") (pinfunction "INTR_77") (pintype "bidirectional"))
    )
    (net (code "217") (name "unconnected-(U2-PMIC_INT-Pad52)") (class "Default")
      (node (ref "U2") (pin "52") (pinfunction "PMIC_INT_52") (pintype "bidirectional"))
    )
    (net (code "218") (name "unconnected-(U2-RESERVED-Pad49)") (class "Default")
      (node (ref "U2") (pin "49") (pinfunction "RESERVED_49") (pintype "bidirectional"))
    )
    (net (code "219") (name "unconnected-(U2-RESERVED-Pad50)") (class "Default")
      (node (ref "U2") (pin "50") (pinfunction "RESERVED_50") (pintype "bidirectional"))
    )
    (net (code "220") (name "unconnected-(U2-RESERVED-Pad84)") (class "Default")
      (node (ref "U2") (pin "84") (pinfunction "RESERVED_84") (pintype "bidirectional"))
    )
    (net (code "221") (name "unconnected-(U2-RESERVED-Pad85)") (class "Default")
      (node (ref "U2") (pin "85") (pinfunction "RESERVED_85") (pintype "bidirectional"))
    )
    (net (code "222") (name "unconnected-(U2-SD_ALRM-Pad82)") (class "Default")
      (node (ref "U2") (pin "82") (pinfunction "SD_ALRM_82") (pintype "bidirectional"))
    )
    (net (code "223") (name "unconnected-(U11-OCS_N1-PadP8)") (class "Default")
      (node (ref "U11") (pin "P8") (pinfunction "OCS_N1_P8") (pintype "bidirectional"))
    )
    (net (code "224") (name "unconnected-(U11-OCS_N2-PadP12)") (class "Default")
      (node (ref "U11") (pin "P12") (pinfunction "OCS_N2_P12") (pintype "bidirectional"))
    )
    (net (code "225") (name "unconnected-(U11-PLLFILT-PadP23)") (class "Default")
      (node (ref "U11") (pin "P23") (pinfunction "PLLFILT_P23") (pintype "passive"))
    )
    (net (code "226") (name "unconnected-(U11-PRTPWR1-PadP7)") (class "Default")
      (node (ref "U11") (pin "P7") (pinfunction "PRTPWR1_P7") (pintype "bidirectional"))
    )
    (net (code "227") (name "unconnected-(U11-PRTPWR2-PadP11)") (class "Default")
      (node (ref "U11") (pin "P11") (pinfunction "PRTPWR2_P11") (pintype "bidirectional"))
    )
    (net (code "228") (name "unconnected-(X1CD-1-Pad172)") (class "Default")
      (node (ref "X1") (pin "172") (pinfunction "1_172") (pintype "passive"))
    )
    (net (code "229") (name "unconnected-(X1CF-1-Pad174)") (class "Default")
      (node (ref "X1") (pin "174") (pinfunction "1_174") (pintype "passive"))
    )
    (net (code "230") (name "unconnected-(X1CH-1-Pad176)") (class "Default")
      (node (ref "X1") (pin "176") (pinfunction "1_176") (pintype "passive"))
    )
    (net (code "231") (name "unconnected-(X1CM-1-Pad180)") (class "Default")
      (node (ref "X1") (pin "180") (pinfunction "1_180") (pintype "passive"))
    )
    (net (code "232") (name "~{RPIBOOT$2}") (class "Default")
      (node (ref "J1") (pin "93") (pinfunction "93_93") (pintype "passive"))
      (node (ref "R5") (pin "1") (pinfunction "1_1") (pintype "passive"))
    )
  )
)
